# electrosteel2020_10_arrange6_synthboards.net
KiCad netlist of a schematic drawn in EAGLE
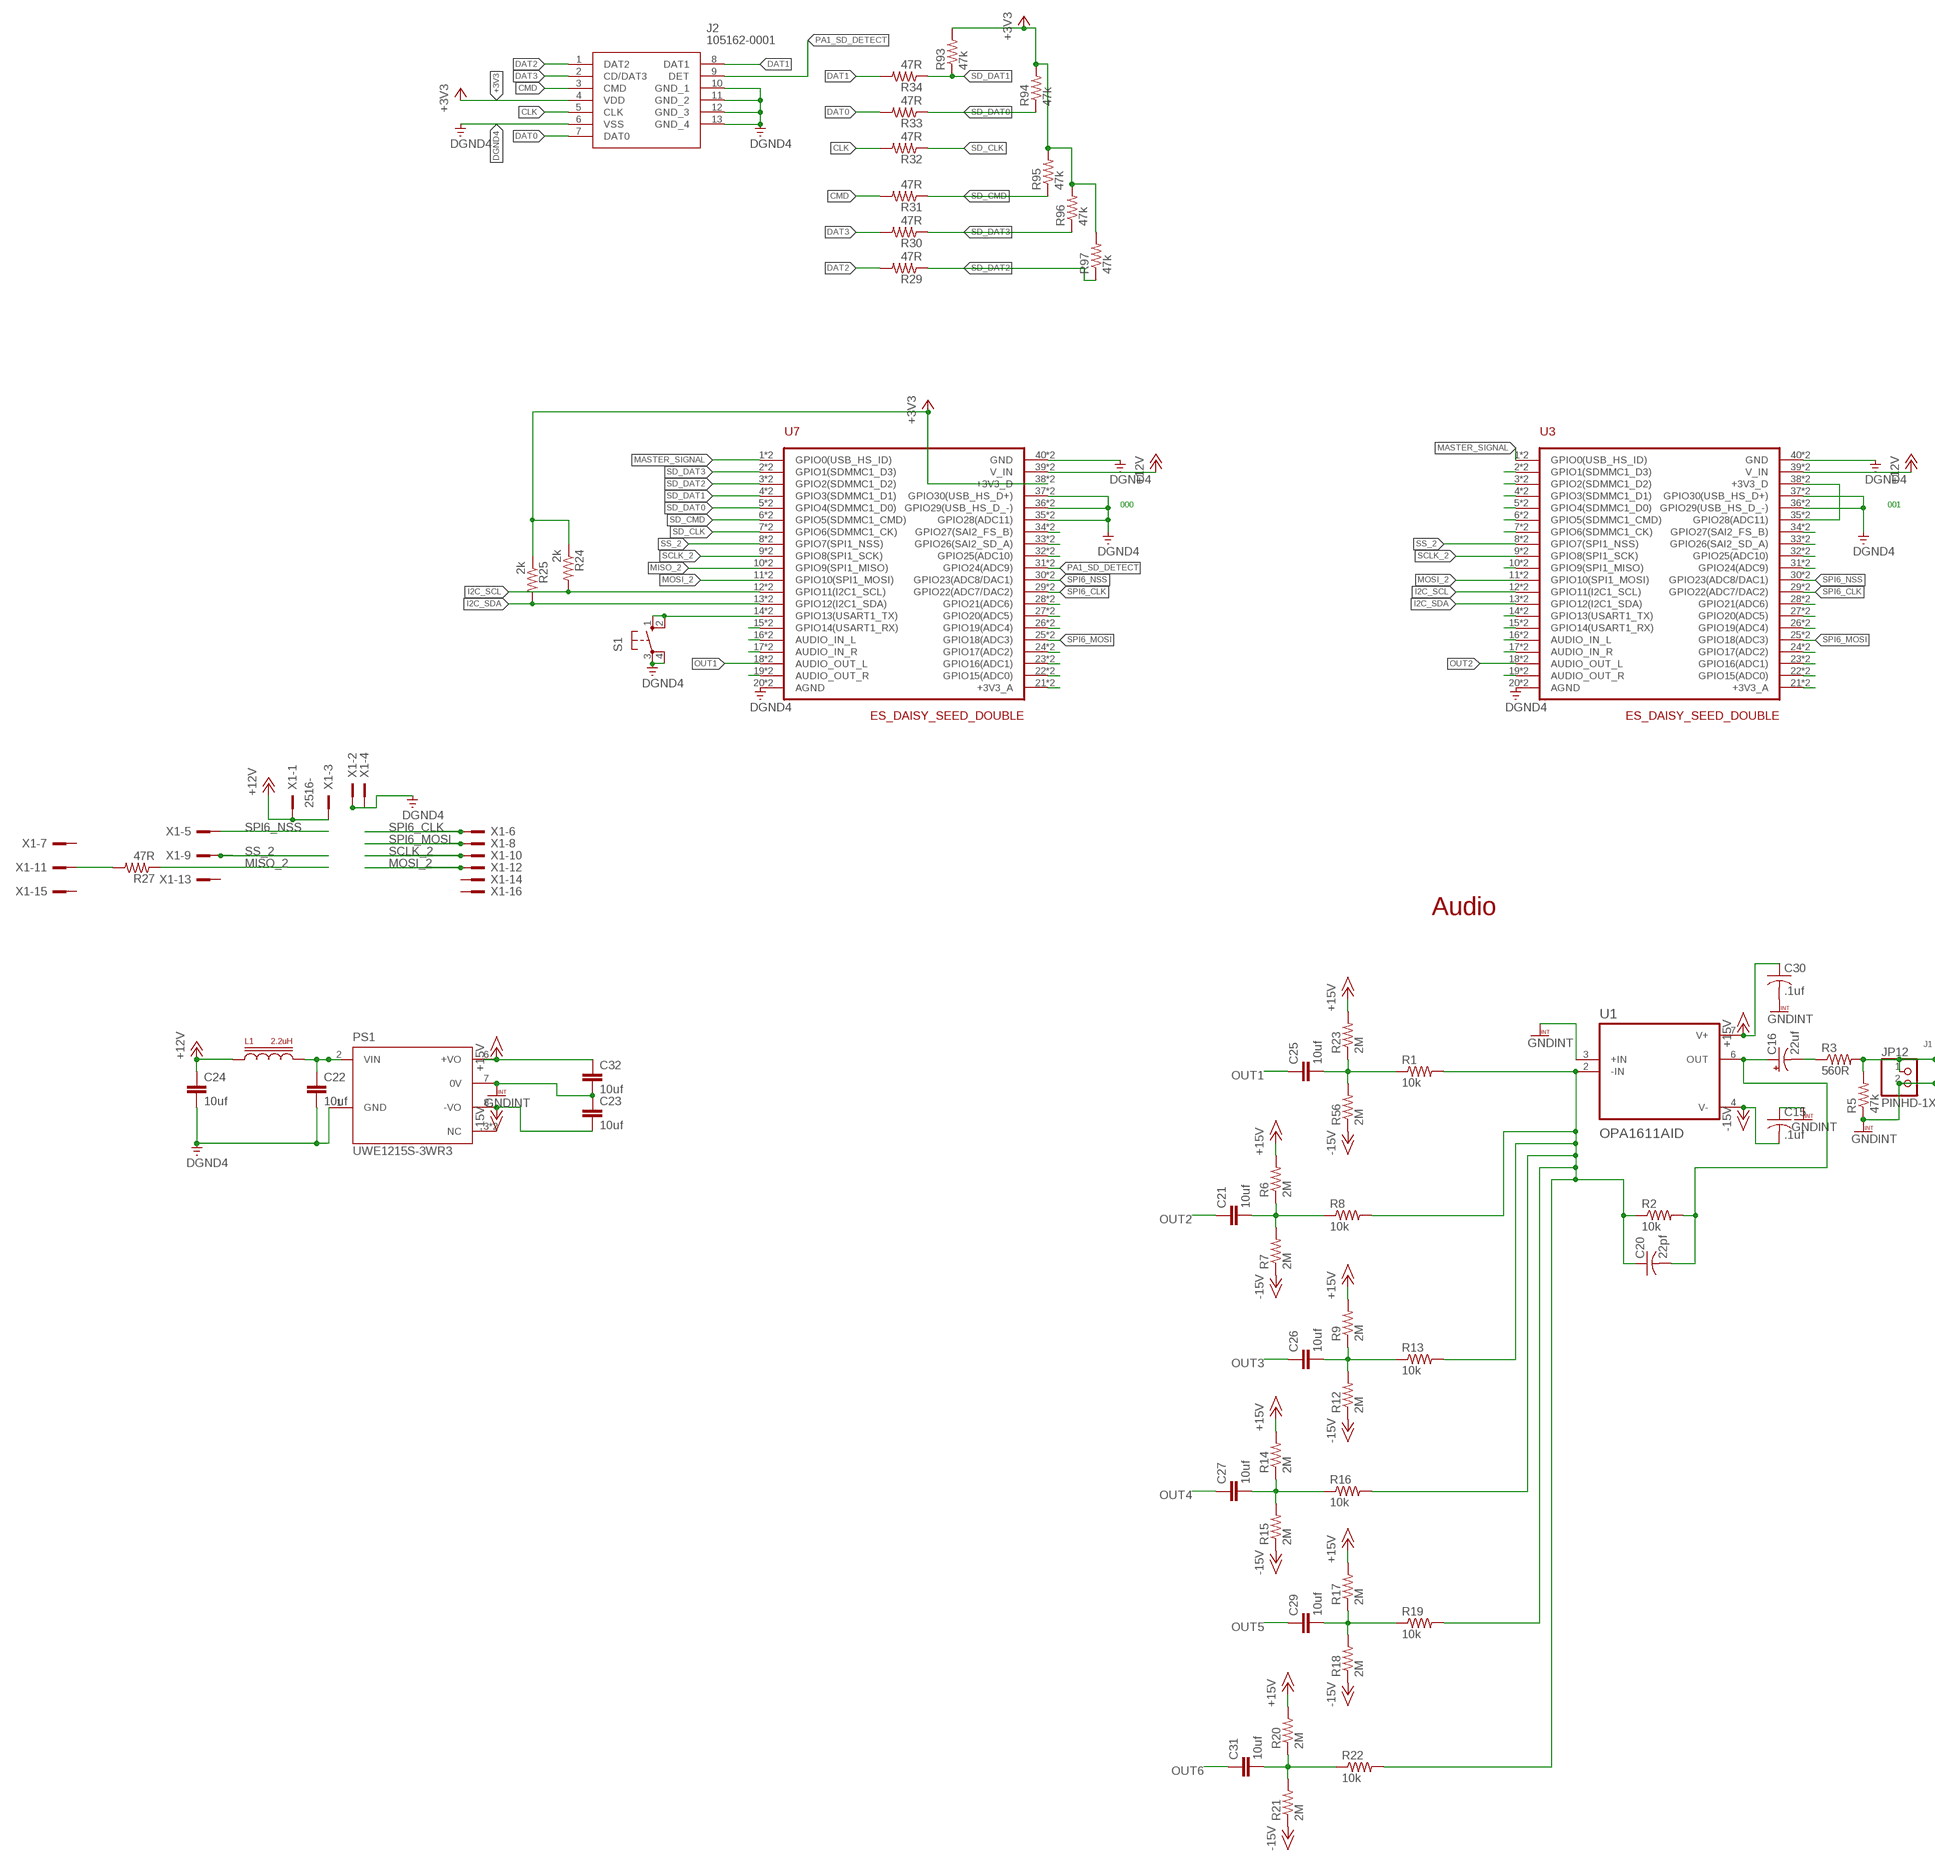
[diagram p0: schematic, sheet 1, part 1 of 2]
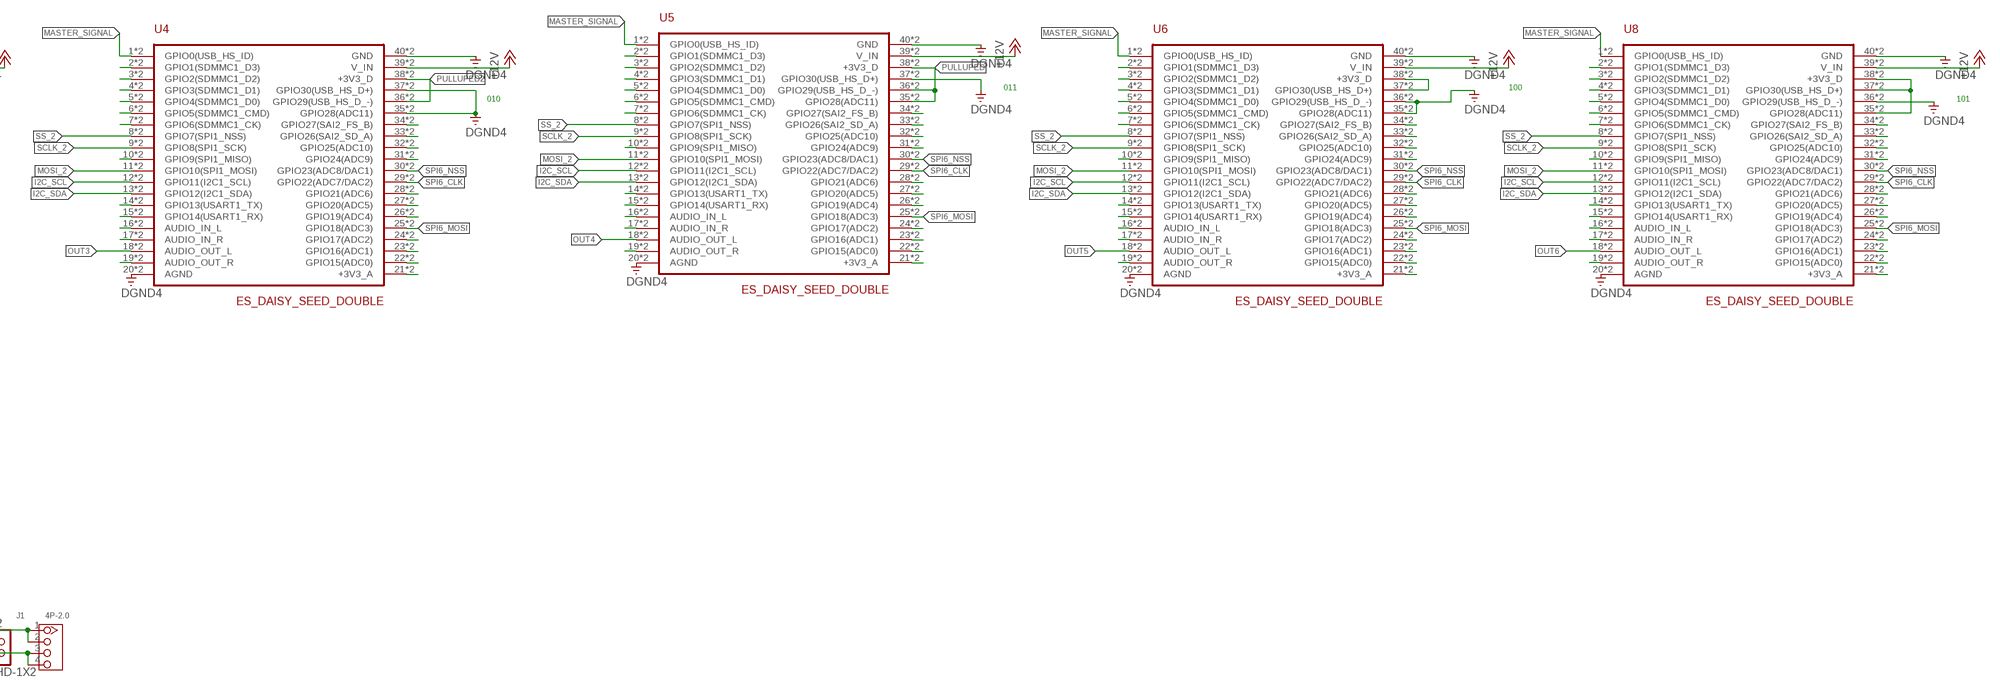
[diagram p1: schematic, sheet 1, part 2 of 2]

(export (version "E")
  (design (tool "Eeschema 10.0.6"))
  (components
    (comp (ref "C15")
      (value ".1uf")
      (footprint "eagle-import:C0603K")
      (fields (field (name "PARTNO") "CC0603KRX7R8BB104"))
      (libsource (lib "eagle-import") (part "C-USC0603K"))
    )
    (comp (ref "C16")
      (value "22uf")
      (footprint "eagle-import:PANASONIC_D")
      (fields (field (name "PARTNO") "EEE-1CA220NP"))
      (libsource (lib "eagle-import") (part "CPOL-USD"))
    )
    (comp (ref "C20")
      (value "22pf")
      (footprint "eagle-import:C0603")
      (fields (field (name "PARTNO") "CC0603JRNPO9BN220"))
      (libsource (lib "eagle-import") (part "rcl_334_C-USC0603"))
    )
    (comp (ref "C21")
      (value "10uf")
      (footprint "eagle-import:C1206K")
      (fields (field (name "PARTNO") "TMK316F106ZL-T"))
      (libsource (lib "eagle-import") (part "C-EUC1206K"))
    )
    (comp (ref "C22")
      (value "10uf")
      (footprint "eagle-import:C1206K")
      (fields (field (name "PARTNO") "TMK316F106ZL-T"))
      (libsource (lib "eagle-import") (part "C-EUC1206K"))
    )
    (comp (ref "C23")
      (value "10uf")
      (footprint "eagle-import:C1206K")
      (fields (field (name "PARTNO") "TMK316F106ZL-T"))
      (libsource (lib "eagle-import") (part "C-EUC1206K"))
    )
    (comp (ref "C24")
      (value "10uf")
      (footprint "eagle-import:C1206K")
      (fields (field (name "PARTNO") "TMK316F106ZL-T"))
      (libsource (lib "eagle-import") (part "C-EUC1206K"))
    )
    (comp (ref "C25")
      (value "10uf")
      (footprint "eagle-import:C1206K")
      (fields (field (name "PARTNO") "TMK316F106ZL-T"))
      (libsource (lib "eagle-import") (part "C-EUC1206K"))
    )
    (comp (ref "C26")
      (value "10uf")
      (footprint "eagle-import:C1206K")
      (fields (field (name "PARTNO") "TMK316F106ZL-T"))
      (libsource (lib "eagle-import") (part "C-EUC1206K"))
    )
    (comp (ref "C27")
      (value "10uf")
      (footprint "eagle-import:C1206K")
      (fields (field (name "PARTNO") "TMK316F106ZL-T"))
      (libsource (lib "eagle-import") (part "C-EUC1206K"))
    )
    (comp (ref "C29")
      (value "10uf")
      (footprint "eagle-import:C1206K")
      (fields (field (name "PARTNO") "TMK316F106ZL-T"))
      (libsource (lib "eagle-import") (part "C-EUC1206K"))
    )
    (comp (ref "C30")
      (value ".1uf")
      (footprint "eagle-import:C0603K")
      (fields (field (name "PARTNO") "CC0603KRX7R8BB104"))
      (libsource (lib "eagle-import") (part "C-USC0603K"))
    )
    (comp (ref "C31")
      (value "10uf")
      (footprint "eagle-import:C1206K")
      (fields (field (name "PARTNO") "TMK316F106ZL-T"))
      (libsource (lib "eagle-import") (part "C-EUC1206K"))
    )
    (comp (ref "C32")
      (value "10uf")
      (footprint "eagle-import:C1206K")
      (fields (field (name "PARTNO") "TMK316F106ZL-T"))
      (libsource (lib "eagle-import") (part "C-EUC1206K"))
    )
    (comp (ref "J1")
      (value "4P-2.0")
      (footprint "eagle-import:HW4-2.0")
      (fields (field (name "PARTNO") "110990030"))
      (libsource (lib "eagle-import") (part "GROVE-CONNECTOR-DIP(4P-2.0)"))
    )
    (comp (ref "J2")
      (value "105162-0001")
      (footprint "eagle-import:105162-0001")
      (fields (field (name "MF") "Molex") (field (name "MP") "1051620001"))
      (libsource (lib "eagle-import") (part "105162-0001"))
    )
    (comp (ref "JP12")
      (value "PINHD-1X2")
      (footprint "eagle-import:1X02")
      (fields (field (name "PARTNO") "*DNP"))
      (libsource (lib "eagle-import") (part "PINHD-1X2"))
    )
    (comp (ref "L1")
      (value "2.2uH")
      (footprint "eagle-import:BOURNS_SRP2010")
      (fields (field (name "PARTNO") "SRP2010-2R2M"))
      (libsource (lib "eagle-import") (part "INDUCTORS"))
    )
    (comp (ref "PS1")
      (value "UWE1215S-3WR3")
      (footprint "eagle-import:CONV_UWE1215S-3WR3")
      (fields
        (field (name "DIGI-KEY_PART_NUMBER") "2725-UWE1215S-3WR3-ND")
        (field (name "MF") "Mornsun America, LLC")
      )
      (libsource (lib "eagle-import") (part "UWE1215S-3WR3"))
    )
    (comp (ref "R1")
      (value "10k")
      (footprint "eagle-import:R0603")
      (fields (field (name "PARTNO") "ESR03EZPF1002"))
      (libsource (lib "eagle-import") (part "Resistor_16378527_R-US_R0603"))
    )
    (comp (ref "R2")
      (value "10k")
      (footprint "eagle-import:R0603")
      (fields (field (name "PARTNO") "ESR03EZPF1002"))
      (libsource (lib "eagle-import") (part "Resistor_16378527_R-US_R0603"))
    )
    (comp (ref "R3")
      (value "560R")
      (footprint "eagle-import:R0603")
      (fields (field (name "PARTNO") "ESR03EZPF5600"))
      (libsource (lib "eagle-import") (part "Resistor_16378527_R-US_R0603"))
    )
    (comp (ref "R5")
      (value "47k")
      (footprint "eagle-import:R0603")
      (fields (field (name "PARTNO") "ESR03EZPJ473"))
      (libsource (lib "eagle-import") (part "Resistor_16378527_R-US_R0603"))
    )
    (comp (ref "R6")
      (value "2M")
      (footprint "eagle-import:R0603")
      (fields (field (name "PARTNO") "RMCF0603FT2M00"))
      (libsource (lib "eagle-import") (part "R-US_R0603"))
    )
    (comp (ref "R7")
      (value "2M")
      (footprint "eagle-import:R0603")
      (fields (field (name "PARTNO") "RMCF0603FT2M00"))
      (libsource (lib "eagle-import") (part "R-US_R0603"))
    )
    (comp (ref "R8")
      (value "10k")
      (footprint "eagle-import:R0603")
      (fields (field (name "PARTNO") "ESR03EZPF1002"))
      (libsource (lib "eagle-import") (part "Resistor_16378527_R-US_R0603"))
    )
    (comp (ref "R9")
      (value "2M")
      (footprint "eagle-import:R0603")
      (fields (field (name "PARTNO") "RMCF0603FT2M00"))
      (libsource (lib "eagle-import") (part "R-US_R0603"))
    )
    (comp (ref "R12")
      (value "2M")
      (footprint "eagle-import:R0603")
      (fields (field (name "PARTNO") "RMCF0603FT2M00"))
      (libsource (lib "eagle-import") (part "R-US_R0603"))
    )
    (comp (ref "R13")
      (value "10k")
      (footprint "eagle-import:R0603")
      (fields (field (name "PARTNO") "ESR03EZPF1002"))
      (libsource (lib "eagle-import") (part "Resistor_16378527_R-US_R0603"))
    )
    (comp (ref "R14")
      (value "2M")
      (footprint "eagle-import:R0603")
      (fields (field (name "PARTNO") "RMCF0603FT2M00"))
      (libsource (lib "eagle-import") (part "R-US_R0603"))
    )
    (comp (ref "R15")
      (value "2M")
      (footprint "eagle-import:R0603")
      (fields (field (name "PARTNO") "RMCF0603FT2M00"))
      (libsource (lib "eagle-import") (part "R-US_R0603"))
    )
    (comp (ref "R16")
      (value "10k")
      (footprint "eagle-import:R0603")
      (fields (field (name "PARTNO") "ESR03EZPF1002"))
      (libsource (lib "eagle-import") (part "Resistor_16378527_R-US_R0603"))
    )
    (comp (ref "R17")
      (value "2M")
      (footprint "eagle-import:R0603")
      (fields (field (name "PARTNO") "RMCF0603FT2M00"))
      (libsource (lib "eagle-import") (part "R-US_R0603"))
    )
    (comp (ref "R18")
      (value "2M")
      (footprint "eagle-import:R0603")
      (fields (field (name "PARTNO") "RMCF0603FT2M00"))
      (libsource (lib "eagle-import") (part "R-US_R0603"))
    )
    (comp (ref "R19")
      (value "10k")
      (footprint "eagle-import:R0603")
      (fields (field (name "PARTNO") "ESR03EZPF1002"))
      (libsource (lib "eagle-import") (part "Resistor_16378527_R-US_R0603"))
    )
    (comp (ref "R20")
      (value "2M")
      (footprint "eagle-import:R0603")
      (fields (field (name "PARTNO") "RMCF0603FT2M00"))
      (libsource (lib "eagle-import") (part "R-US_R0603"))
    )
    (comp (ref "R21")
      (value "2M")
      (footprint "eagle-import:R0603")
      (fields (field (name "PARTNO") "RMCF0603FT2M00"))
      (libsource (lib "eagle-import") (part "R-US_R0603"))
    )
    (comp (ref "R22")
      (value "10k")
      (footprint "eagle-import:R0603")
      (fields (field (name "PARTNO") "ESR03EZPF1002"))
      (libsource (lib "eagle-import") (part "Resistor_16378527_R-US_R0603"))
    )
    (comp (ref "R23")
      (value "2M")
      (footprint "eagle-import:R0603")
      (fields (field (name "PARTNO") "RMCF0603FT2M00"))
      (libsource (lib "eagle-import") (part "R-US_R0603"))
    )
    (comp (ref "R24")
      (value "2k")
      (footprint "eagle-import:R0603")
      (fields (field (name "PARTNO") "ERJ-PA3F2001V"))
      (libsource (lib "eagle-import") (part "rcl_334_R-US_R0603"))
    )
    (comp (ref "R25")
      (value "2k")
      (footprint "eagle-import:R0603")
      (fields (field (name "PARTNO") "ERJ-PA3F2001V"))
      (libsource (lib "eagle-import") (part "rcl_334_R-US_R0603"))
    )
    (comp (ref "R27")
      (value "47R")
      (footprint "eagle-import:R0603")
      (fields (field (name "PARTNO") "RC0603JR-0747RL"))
      (libsource (lib "eagle-import") (part "rcl_334_R-US_R0603"))
    )
    (comp (ref "R29")
      (value "47R")
      (footprint "eagle-import:R0603")
      (fields (field (name "PARTNO") "RC0603JR-0747RL"))
      (libsource (lib "eagle-import") (part "rcl_334_R-US_R0603"))
    )
    (comp (ref "R30")
      (value "47R")
      (footprint "eagle-import:R0603")
      (fields (field (name "PARTNO") "RC0603JR-0747RL"))
      (libsource (lib "eagle-import") (part "rcl_334_R-US_R0603"))
    )
    (comp (ref "R31")
      (value "47R")
      (footprint "eagle-import:R0603")
      (fields (field (name "PARTNO") "RC0603JR-0747RL"))
      (libsource (lib "eagle-import") (part "rcl_334_R-US_R0603"))
    )
    (comp (ref "R32")
      (value "47R")
      (footprint "eagle-import:R0603")
      (fields (field (name "PARTNO") "RC0603JR-0747RL"))
      (libsource (lib "eagle-import") (part "rcl_334_R-US_R0603"))
    )
    (comp (ref "R33")
      (value "47R")
      (footprint "eagle-import:R0603")
      (fields (field (name "PARTNO") "RC0603JR-0747RL"))
      (libsource (lib "eagle-import") (part "rcl_334_R-US_R0603"))
    )
    (comp (ref "R34")
      (value "47R")
      (footprint "eagle-import:R0603")
      (fields (field (name "PARTNO") "RC0603JR-0747RL"))
      (libsource (lib "eagle-import") (part "rcl_334_R-US_R0603"))
    )
    (comp (ref "R56")
      (value "2M")
      (footprint "eagle-import:R0603")
      (fields (field (name "PARTNO") "RMCF0603FT2M00"))
      (libsource (lib "eagle-import") (part "R-US_R0603"))
    )
    (comp (ref "R93")
      (value "47k")
      (footprint "eagle-import:R0603")
      (fields (field (name "PARTNO") "ESR03EZPJ473"))
      (libsource (lib "eagle-import") (part "rcl_R-US_R0603"))
    )
    (comp (ref "R94")
      (value "47k")
      (footprint "eagle-import:R0603")
      (fields (field (name "PARTNO") "ESR03EZPJ473"))
      (libsource (lib "eagle-import") (part "rcl_R-US_R0603"))
    )
    (comp (ref "R95")
      (value "47k")
      (footprint "eagle-import:R0603")
      (fields (field (name "PARTNO") "ESR03EZPJ473"))
      (libsource (lib "eagle-import") (part "rcl_R-US_R0603"))
    )
    (comp (ref "R96")
      (value "47k")
      (footprint "eagle-import:R0603")
      (fields (field (name "PARTNO") "ESR03EZPJ473"))
      (libsource (lib "eagle-import") (part "rcl_R-US_R0603"))
    )
    (comp (ref "R97")
      (value "47k")
      (footprint "eagle-import:R0603")
      (fields (field (name "PARTNO") "ESR03EZPJ473"))
      (libsource (lib "eagle-import") (part "rcl_R-US_R0603"))
    )
    (comp (ref "S1")
      (value "10-XX")
      (footprint "eagle-import:B3F-10XX")
      (fields (field (name "MPN") "B3F-1000"))
      (libsource (lib "eagle-import") (part "10-XX"))
    )
    (comp (ref "U1")
      (value "OPA1611AID")
      (footprint "eagle-import:SOIC127P599X175-8N")
      (fields (field (name "DIGI-KEY_PART_NUMBER") "296-24958-5-ND") (field (name "MF") "Texas Instruments"))
      (libsource (lib "eagle-import") (part "OPA1611AID"))
    )
    (comp (ref "U3")
      (value "ES_DAISY_SEED_DOUBLE")
      (footprint "eagle-import:ES_DAISY_SEED_DOUBLE")
      (fields (field (name "PARTNO") "4840-6004-CP"))
      (libsource (lib "eagle-import") (part "ES_DAISY_SEED_DOUBLE"))
    )
    (comp (ref "U4")
      (value "ES_DAISY_SEED_DOUBLE")
      (footprint "eagle-import:ES_DAISY_SEED_DOUBLE")
      (fields (field (name "PARTNO") "4840-6004-CP"))
      (libsource (lib "eagle-import") (part "ES_DAISY_SEED_DOUBLE"))
    )
    (comp (ref "U5")
      (value "ES_DAISY_SEED_DOUBLE")
      (footprint "eagle-import:ES_DAISY_SEED_DOUBLE")
      (fields (field (name "PARTNO") "4840-6004-CP"))
      (libsource (lib "eagle-import") (part "ES_DAISY_SEED_DOUBLE"))
    )
    (comp (ref "U6")
      (value "ES_DAISY_SEED_DOUBLE")
      (footprint "eagle-import:ES_DAISY_SEED_DOUBLE")
      (fields (field (name "PARTNO") "4840-6004-CP"))
      (libsource (lib "eagle-import") (part "ES_DAISY_SEED_DOUBLE"))
    )
    (comp (ref "U7")
      (value "ES_DAISY_SEED_DOUBLE")
      (footprint "eagle-import:ES_DAISY_SEED_DOUBLE")
      (fields (field (name "PARTNO") "4840-6004-CP"))
      (libsource (lib "eagle-import") (part "ES_DAISY_SEED_DOUBLE"))
    )
    (comp (ref "U8")
      (value "ES_DAISY_SEED_DOUBLE")
      (footprint "eagle-import:ES_DAISY_SEED_DOUBLE")
      (fields (field (name "PARTNO") "4840-6004-CP"))
      (libsource (lib "eagle-import") (part "ES_DAISY_SEED_DOUBLE"))
    )
    (comp (ref "X1")
      (value "2516-")
      (footprint "eagle-import:PAK100_2500-16")
      (fields (field (name "PARTNO") "SBH11-PBPC-D08-ST-BK"))
      (libsource (lib "eagle-import") (part "2516-"))
    )
  )
  (nets
    (net (code "1") (name "+3V3") (class "Default")
      (node (ref "J2") (pin "4") (pinfunction "VDD_4") (pintype "bidirectional"))
      (node (ref "R24") (pin "1") (pinfunction "1_1") (pintype "passive"))
      (node (ref "R25") (pin "1") (pinfunction "1_1") (pintype "passive"))
      (node (ref "R93") (pin "2") (pinfunction "2_2") (pintype "passive"))
      (node (ref "R94") (pin "2") (pinfunction "2_2") (pintype "passive"))
      (node (ref "R95") (pin "2") (pinfunction "2_2") (pintype "passive"))
      (node (ref "R96") (pin "2") (pinfunction "2_2") (pintype "passive"))
      (node (ref "R97") (pin "2") (pinfunction "2_2") (pintype "passive"))
      (node (ref "U7") (pin "38") (pinfunction "+3V3_D_38") (pintype "bidirectional"))
      (node (ref "U7") (pin "B38") (pinfunction "+3V3_D_B38") (pintype "bidirectional"))
    )
    (net (code "2") (name "+12V") (class "Default")
      (node (ref "C24") (pin "1") (pinfunction "1_1") (pintype "passive"))
      (node (ref "L1") (pin "P$1") (pinfunction "P$1_P$1") (pintype "bidirectional"))
      (node (ref "U3") (pin "39") (pinfunction "V_IN_39") (pintype "bidirectional"))
      (node (ref "U3") (pin "B39") (pinfunction "V_IN_B39") (pintype "bidirectional"))
      (node (ref "U4") (pin "39") (pinfunction "V_IN_39") (pintype "bidirectional"))
      (node (ref "U4") (pin "B39") (pinfunction "V_IN_B39") (pintype "bidirectional"))
      (node (ref "U5") (pin "39") (pinfunction "V_IN_39") (pintype "bidirectional"))
      (node (ref "U5") (pin "B39") (pinfunction "V_IN_B39") (pintype "bidirectional"))
      (node (ref "U6") (pin "39") (pinfunction "V_IN_39") (pintype "bidirectional"))
      (node (ref "U6") (pin "B39") (pinfunction "V_IN_B39") (pintype "bidirectional"))
      (node (ref "U7") (pin "39") (pinfunction "V_IN_39") (pintype "bidirectional"))
      (node (ref "U7") (pin "B39") (pinfunction "V_IN_B39") (pintype "bidirectional"))
      (node (ref "U8") (pin "39") (pinfunction "V_IN_39") (pintype "bidirectional"))
      (node (ref "U8") (pin "B39") (pinfunction "V_IN_B39") (pintype "bidirectional"))
      (node (ref "X1") (pin "1") (pinfunction "KL_1") (pintype "passive"))
      (node (ref "X1") (pin "3") (pinfunction "KL_3") (pintype "passive"))
    )
    (net (code "3") (name "+15V") (class "Default")
      (node (ref "C30") (pin "1") (pinfunction "1_1") (pintype "passive"))
      (node (ref "C32") (pin "1") (pinfunction "1_1") (pintype "passive"))
      (node (ref "PS1") (pin "6") (pinfunction "+VO_6") (pintype "output"))
      (node (ref "R14") (pin "2") (pinfunction "2_2") (pintype "passive"))
      (node (ref "R17") (pin "2") (pinfunction "2_2") (pintype "passive"))
      (node (ref "R20") (pin "2") (pinfunction "2_2") (pintype "passive"))
      (node (ref "R23") (pin "2") (pinfunction "2_2") (pintype "passive"))
      (node (ref "R6") (pin "2") (pinfunction "2_2") (pintype "passive"))
      (node (ref "R9") (pin "2") (pinfunction "2_2") (pintype "passive"))
      (node (ref "U1") (pin "7") (pinfunction "V+_7") (pintype "power_in"))
    )
    (net (code "4") (name "-15V") (class "Default")
      (node (ref "C15") (pin "2") (pinfunction "2_2") (pintype "passive"))
      (node (ref "C23") (pin "2") (pinfunction "2_2") (pintype "passive"))
      (node (ref "PS1") (pin "8") (pinfunction "-VO_8") (pintype "output"))
      (node (ref "R12") (pin "1") (pinfunction "1_1") (pintype "passive"))
      (node (ref "R15") (pin "1") (pinfunction "1_1") (pintype "passive"))
      (node (ref "R18") (pin "1") (pinfunction "1_1") (pintype "passive"))
      (node (ref "R21") (pin "1") (pinfunction "1_1") (pintype "passive"))
      (node (ref "R56") (pin "1") (pinfunction "1_1") (pintype "passive"))
      (node (ref "R7") (pin "1") (pinfunction "1_1") (pintype "passive"))
      (node (ref "U1") (pin "4") (pinfunction "V-_4") (pintype "power_in"))
    )
    (net (code "5") (name "CLK") (class "Default")
      (node (ref "J2") (pin "5") (pinfunction "CLK_5") (pintype "bidirectional"))
      (node (ref "R32") (pin "2") (pinfunction "2_2") (pintype "passive"))
    )
    (net (code "6") (name "CMD") (class "Default")
      (node (ref "J2") (pin "3") (pinfunction "CMD_3") (pintype "bidirectional"))
      (node (ref "R31") (pin "2") (pinfunction "2_2") (pintype "passive"))
    )
    (net (code "7") (name "DAT0") (class "Default")
      (node (ref "J2") (pin "7") (pinfunction "DAT0_7") (pintype "bidirectional"))
      (node (ref "R33") (pin "2") (pinfunction "2_2") (pintype "passive"))
    )
    (net (code "8") (name "DAT1") (class "Default")
      (node (ref "J2") (pin "8") (pinfunction "DAT1_8") (pintype "bidirectional"))
      (node (ref "R34") (pin "2") (pinfunction "2_2") (pintype "passive"))
    )
    (net (code "9") (name "DAT2") (class "Default")
      (node (ref "J2") (pin "1") (pinfunction "DAT2_1") (pintype "bidirectional"))
      (node (ref "R29") (pin "2") (pinfunction "2_2") (pintype "passive"))
    )
    (net (code "10") (name "DAT3") (class "Default")
      (node (ref "J2") (pin "2") (pinfunction "CD/DAT3_2") (pintype "bidirectional"))
      (node (ref "R30") (pin "2") (pinfunction "2_2") (pintype "passive"))
    )
    (net (code "11") (name "DGND4") (class "Default")
      (node (ref "C22") (pin "2") (pinfunction "2_2") (pintype "passive"))
      (node (ref "C24") (pin "2") (pinfunction "2_2") (pintype "passive"))
      (node (ref "J2") (pin "10") (pinfunction "GND_1_10") (pintype "bidirectional"))
      (node (ref "J2") (pin "11") (pinfunction "GND_2_11") (pintype "bidirectional"))
      (node (ref "J2") (pin "12") (pinfunction "GND_3_12") (pintype "bidirectional"))
      (node (ref "J2") (pin "13") (pinfunction "GND_4_13") (pintype "bidirectional"))
      (node (ref "J2") (pin "6") (pinfunction "VSS_6") (pintype "bidirectional"))
      (node (ref "PS1") (pin "1") (pinfunction "GND_1") (pintype "power_in"))
      (node (ref "S1") (pin "3") (pinfunction "P_3") (pintype "passive"))
      (node (ref "S1") (pin "4") (pinfunction "P1_4") (pintype "passive"))
      (node (ref "U3") (pin "20") (pinfunction "AGND_20") (pintype "bidirectional"))
      (node (ref "U3") (pin "36") (pinfunction "GPIO29(USB_HS_D_-)_36") (pintype "bidirectional"))
      (node (ref "U3") (pin "37") (pinfunction "GPIO30(USB_HS_D+)_37") (pintype "bidirectional"))
      (node (ref "U3") (pin "40") (pinfunction "GND_40") (pintype "bidirectional"))
      (node (ref "U3") (pin "B20") (pinfunction "AGND_B20") (pintype "bidirectional"))
      (node (ref "U3") (pin "B36") (pinfunction "GPIO29(USB_HS_D_-)_B36") (pintype "bidirectional"))
      (node (ref "U3") (pin "B37") (pinfunction "GPIO30(USB_HS_D+)_B37") (pintype "bidirectional"))
      (node (ref "U3") (pin "B40") (pinfunction "GND_B40") (pintype "bidirectional"))
      (node (ref "U4") (pin "20") (pinfunction "AGND_20") (pintype "bidirectional"))
      (node (ref "U4") (pin "35") (pinfunction "GPIO28(ADC11)_35") (pintype "bidirectional"))
      (node (ref "U4") (pin "37") (pinfunction "GPIO30(USB_HS_D+)_37") (pintype "bidirectional"))
      (node (ref "U4") (pin "40") (pinfunction "GND_40") (pintype "bidirectional"))
      (node (ref "U4") (pin "B20") (pinfunction "AGND_B20") (pintype "bidirectional"))
      (node (ref "U4") (pin "B35") (pinfunction "GPIO28(ADC11)_B35") (pintype "bidirectional"))
      (node (ref "U4") (pin "B37") (pinfunction "GPIO30(USB_HS_D+)_B37") (pintype "bidirectional"))
      (node (ref "U4") (pin "B40") (pinfunction "GND_B40") (pintype "bidirectional"))
      (node (ref "U5") (pin "20") (pinfunction "AGND_20") (pintype "bidirectional"))
      (node (ref "U5") (pin "37") (pinfunction "GPIO30(USB_HS_D+)_37") (pintype "bidirectional"))
      (node (ref "U5") (pin "40") (pinfunction "GND_40") (pintype "bidirectional"))
      (node (ref "U5") (pin "B20") (pinfunction "AGND_B20") (pintype "bidirectional"))
      (node (ref "U5") (pin "B37") (pinfunction "GPIO30(USB_HS_D+)_B37") (pintype "bidirectional"))
      (node (ref "U5") (pin "B40") (pinfunction "GND_B40") (pintype "bidirectional"))
      (node (ref "U6") (pin "20") (pinfunction "AGND_20") (pintype "bidirectional"))
      (node (ref "U6") (pin "35") (pinfunction "GPIO28(ADC11)_35") (pintype "bidirectional"))
      (node (ref "U6") (pin "36") (pinfunction "GPIO29(USB_HS_D_-)_36") (pintype "bidirectional"))
      (node (ref "U6") (pin "40") (pinfunction "GND_40") (pintype "bidirectional"))
      (node (ref "U6") (pin "B20") (pinfunction "AGND_B20") (pintype "bidirectional"))
      (node (ref "U6") (pin "B35") (pinfunction "GPIO28(ADC11)_B35") (pintype "bidirectional"))
      (node (ref "U6") (pin "B36") (pinfunction "GPIO29(USB_HS_D_-)_B36") (pintype "bidirectional"))
      (node (ref "U6") (pin "B40") (pinfunction "GND_B40") (pintype "bidirectional"))
      (node (ref "U7") (pin "20") (pinfunction "AGND_20") (pintype "bidirectional"))
      (node (ref "U7") (pin "35") (pinfunction "GPIO28(ADC11)_35") (pintype "bidirectional"))
      (node (ref "U7") (pin "36") (pinfunction "GPIO29(USB_HS_D_-)_36") (pintype "bidirectional"))
      (node (ref "U7") (pin "37") (pinfunction "GPIO30(USB_HS_D+)_37") (pintype "bidirectional"))
      (node (ref "U7") (pin "40") (pinfunction "GND_40") (pintype "bidirectional"))
      (node (ref "U7") (pin "B20") (pinfunction "AGND_B20") (pintype "bidirectional"))
      (node (ref "U7") (pin "B35") (pinfunction "GPIO28(ADC11)_B35") (pintype "bidirectional"))
      (node (ref "U7") (pin "B36") (pinfunction "GPIO29(USB_HS_D_-)_B36") (pintype "bidirectional"))
      (node (ref "U7") (pin "B37") (pinfunction "GPIO30(USB_HS_D+)_B37") (pintype "bidirectional"))
      (node (ref "U7") (pin "B40") (pinfunction "GND_B40") (pintype "bidirectional"))
      (node (ref "U8") (pin "20") (pinfunction "AGND_20") (pintype "bidirectional"))
      (node (ref "U8") (pin "36") (pinfunction "GPIO29(USB_HS_D_-)_36") (pintype "bidirectional"))
      (node (ref "U8") (pin "40") (pinfunction "GND_40") (pintype "bidirectional"))
      (node (ref "U8") (pin "B20") (pinfunction "AGND_B20") (pintype "bidirectional"))
      (node (ref "U8") (pin "B36") (pinfunction "GPIO29(USB_HS_D_-)_B36") (pintype "bidirectional"))
      (node (ref "U8") (pin "B40") (pinfunction "GND_B40") (pintype "bidirectional"))
      (node (ref "X1") (pin "2") (pinfunction "KL_2") (pintype "passive"))
      (node (ref "X1") (pin "4") (pinfunction "KL_4") (pintype "passive"))
    )
    (net (code "12") (name "GNDINT") (class "Default")
      (node (ref "C15") (pin "1") (pinfunction "1_1") (pintype "passive"))
      (node (ref "C23") (pin "1") (pinfunction "1_1") (pintype "passive"))
      (node (ref "C30") (pin "2") (pinfunction "2_2") (pintype "passive"))
      (node (ref "C32") (pin "2") (pinfunction "2_2") (pintype "passive"))
      (node (ref "J1") (pin "3") (pinfunction "3_3") (pintype "bidirectional"))
      (node (ref "J1") (pin "4") (pinfunction "4_4") (pintype "bidirectional"))
      (node (ref "JP12") (pin "2") (pinfunction "2_2") (pintype "passive"))
      (node (ref "PS1") (pin "7") (pinfunction "0V_7") (pintype "passive"))
      (node (ref "R5") (pin "1") (pinfunction "1_1") (pintype "passive"))
      (node (ref "U1") (pin "3") (pinfunction "+IN_3") (pintype "input"))
    )
    (net (code "13") (name "I2C_SCL") (class "Default")
      (node (ref "R24") (pin "2") (pinfunction "2_2") (pintype "passive"))
      (node (ref "U3") (pin "12") (pinfunction "GPIO11(I2C1_SCL)_12") (pintype "bidirectional"))
      (node (ref "U3") (pin "B12") (pinfunction "GPIO11(I2C1_SCL)_B12") (pintype "bidirectional"))
      (node (ref "U4") (pin "12") (pinfunction "GPIO11(I2C1_SCL)_12") (pintype "bidirectional"))
      (node (ref "U4") (pin "B12") (pinfunction "GPIO11(I2C1_SCL)_B12") (pintype "bidirectional"))
      (node (ref "U5") (pin "12") (pinfunction "GPIO11(I2C1_SCL)_12") (pintype "bidirectional"))
      (node (ref "U5") (pin "B12") (pinfunction "GPIO11(I2C1_SCL)_B12") (pintype "bidirectional"))
      (node (ref "U6") (pin "12") (pinfunction "GPIO11(I2C1_SCL)_12") (pintype "bidirectional"))
      (node (ref "U6") (pin "B12") (pinfunction "GPIO11(I2C1_SCL)_B12") (pintype "bidirectional"))
      (node (ref "U7") (pin "12") (pinfunction "GPIO11(I2C1_SCL)_12") (pintype "bidirectional"))
      (node (ref "U7") (pin "B12") (pinfunction "GPIO11(I2C1_SCL)_B12") (pintype "bidirectional"))
      (node (ref "U8") (pin "12") (pinfunction "GPIO11(I2C1_SCL)_12") (pintype "bidirectional"))
      (node (ref "U8") (pin "B12") (pinfunction "GPIO11(I2C1_SCL)_B12") (pintype "bidirectional"))
    )
    (net (code "14") (name "I2C_SDA") (class "Default")
      (node (ref "R25") (pin "2") (pinfunction "2_2") (pintype "passive"))
      (node (ref "U3") (pin "13") (pinfunction "GPIO12(I2C1_SDA)_13") (pintype "bidirectional"))
      (node (ref "U3") (pin "B13") (pinfunction "GPIO12(I2C1_SDA)_B13") (pintype "bidirectional"))
      (node (ref "U4") (pin "13") (pinfunction "GPIO12(I2C1_SDA)_13") (pintype "bidirectional"))
      (node (ref "U4") (pin "B13") (pinfunction "GPIO12(I2C1_SDA)_B13") (pintype "bidirectional"))
      (node (ref "U5") (pin "13") (pinfunction "GPIO12(I2C1_SDA)_13") (pintype "bidirectional"))
      (node (ref "U5") (pin "B13") (pinfunction "GPIO12(I2C1_SDA)_B13") (pintype "bidirectional"))
      (node (ref "U6") (pin "13") (pinfunction "GPIO12(I2C1_SDA)_13") (pintype "bidirectional"))
      (node (ref "U6") (pin "B13") (pinfunction "GPIO12(I2C1_SDA)_B13") (pintype "bidirectional"))
      (node (ref "U7") (pin "13") (pinfunction "GPIO12(I2C1_SDA)_13") (pintype "bidirectional"))
      (node (ref "U7") (pin "B13") (pinfunction "GPIO12(I2C1_SDA)_B13") (pintype "bidirectional"))
      (node (ref "U8") (pin "13") (pinfunction "GPIO12(I2C1_SDA)_13") (pintype "bidirectional"))
      (node (ref "U8") (pin "B13") (pinfunction "GPIO12(I2C1_SDA)_B13") (pintype "bidirectional"))
    )
    (net (code "15") (name "MASTER_SIGNAL") (class "Default")
      (node (ref "U3") (pin "1") (pinfunction "GPIO0(USB_HS_ID)_1") (pintype "bidirectional"))
      (node (ref "U3") (pin "B1") (pinfunction "GPIO0(USB_HS_ID)_B1") (pintype "bidirectional"))
      (node (ref "U4") (pin "1") (pinfunction "GPIO0(USB_HS_ID)_1") (pintype "bidirectional"))
      (node (ref "U4") (pin "B1") (pinfunction "GPIO0(USB_HS_ID)_B1") (pintype "bidirectional"))
      (node (ref "U5") (pin "1") (pinfunction "GPIO0(USB_HS_ID)_1") (pintype "bidirectional"))
      (node (ref "U5") (pin "B1") (pinfunction "GPIO0(USB_HS_ID)_B1") (pintype "bidirectional"))
      (node (ref "U6") (pin "1") (pinfunction "GPIO0(USB_HS_ID)_1") (pintype "bidirectional"))
      (node (ref "U6") (pin "B1") (pinfunction "GPIO0(USB_HS_ID)_B1") (pintype "bidirectional"))
      (node (ref "U7") (pin "1") (pinfunction "GPIO0(USB_HS_ID)_1") (pintype "bidirectional"))
      (node (ref "U7") (pin "B1") (pinfunction "GPIO0(USB_HS_ID)_B1") (pintype "bidirectional"))
      (node (ref "U8") (pin "1") (pinfunction "GPIO0(USB_HS_ID)_1") (pintype "bidirectional"))
      (node (ref "U8") (pin "B1") (pinfunction "GPIO0(USB_HS_ID)_B1") (pintype "bidirectional"))
    )
    (net (code "16") (name "MISO_2") (class "Default")
      (node (ref "R27") (pin "1") (pinfunction "1_1") (pintype "passive"))
      (node (ref "U7") (pin "10") (pinfunction "GPIO9(SPI1_MISO)_10") (pintype "bidirectional"))
      (node (ref "U7") (pin "B10") (pinfunction "GPIO9(SPI1_MISO)_B10") (pintype "bidirectional"))
    )
    (net (code "17") (name "MOSI_2") (class "Default")
      (node (ref "U3") (pin "11") (pinfunction "GPIO10(SPI1_MOSI)_11") (pintype "bidirectional"))
      (node (ref "U3") (pin "B11") (pinfunction "GPIO10(SPI1_MOSI)_B11") (pintype "bidirectional"))
      (node (ref "U4") (pin "11") (pinfunction "GPIO10(SPI1_MOSI)_11") (pintype "bidirectional"))
      (node (ref "U4") (pin "B11") (pinfunction "GPIO10(SPI1_MOSI)_B11") (pintype "bidirectional"))
      (node (ref "U5") (pin "11") (pinfunction "GPIO10(SPI1_MOSI)_11") (pintype "bidirectional"))
      (node (ref "U5") (pin "B11") (pinfunction "GPIO10(SPI1_MOSI)_B11") (pintype "bidirectional"))
      (node (ref "U6") (pin "11") (pinfunction "GPIO10(SPI1_MOSI)_11") (pintype "bidirectional"))
      (node (ref "U6") (pin "B11") (pinfunction "GPIO10(SPI1_MOSI)_B11") (pintype "bidirectional"))
      (node (ref "U7") (pin "11") (pinfunction "GPIO10(SPI1_MOSI)_11") (pintype "bidirectional"))
      (node (ref "U7") (pin "B11") (pinfunction "GPIO10(SPI1_MOSI)_B11") (pintype "bidirectional"))
      (node (ref "U8") (pin "11") (pinfunction "GPIO10(SPI1_MOSI)_11") (pintype "bidirectional"))
      (node (ref "U8") (pin "B11") (pinfunction "GPIO10(SPI1_MOSI)_B11") (pintype "bidirectional"))
      (node (ref "X1") (pin "12") (pinfunction "KL_12") (pintype "passive"))
    )
    (net (code "18") (name "Net-(C16-Pad-)") (class "Default")
      (node (ref "C16") (pin "-") (pinfunction "-_-") (pintype "passive"))
      (node (ref "R3") (pin "1") (pinfunction "1_1") (pintype "passive"))
    )
    (net (code "19") (name "Net-(C21-Pad2)") (class "Default")
      (node (ref "C21") (pin "2") (pinfunction "2_2") (pintype "passive"))
      (node (ref "R6") (pin "1") (pinfunction "1_1") (pintype "passive"))
      (node (ref "R7") (pin "2") (pinfunction "2_2") (pintype "passive"))
      (node (ref "R8") (pin "1") (pinfunction "1_1") (pintype "passive"))
    )
    (net (code "20") (name "Net-(C25-Pad2)") (class "Default")
      (node (ref "C25") (pin "2") (pinfunction "2_2") (pintype "passive"))
      (node (ref "R1") (pin "1") (pinfunction "1_1") (pintype "passive"))
      (node (ref "R23") (pin "1") (pinfunction "1_1") (pintype "passive"))
      (node (ref "R56") (pin "2") (pinfunction "2_2") (pintype "passive"))
    )
    (net (code "21") (name "Net-(C26-Pad2)") (class "Default")
      (node (ref "C26") (pin "2") (pinfunction "2_2") (pintype "passive"))
      (node (ref "R12") (pin "2") (pinfunction "2_2") (pintype "passive"))
      (node (ref "R13") (pin "1") (pinfunction "1_1") (pintype "passive"))
      (node (ref "R9") (pin "1") (pinfunction "1_1") (pintype "passive"))
    )
    (net (code "22") (name "Net-(C27-Pad2)") (class "Default")
      (node (ref "C27") (pin "2") (pinfunction "2_2") (pintype "passive"))
      (node (ref "R14") (pin "1") (pinfunction "1_1") (pintype "passive"))
      (node (ref "R15") (pin "2") (pinfunction "2_2") (pintype "passive"))
      (node (ref "R16") (pin "1") (pinfunction "1_1") (pintype "passive"))
    )
    (net (code "23") (name "Net-(C29-Pad2)") (class "Default")
      (node (ref "C29") (pin "2") (pinfunction "2_2") (pintype "passive"))
      (node (ref "R17") (pin "1") (pinfunction "1_1") (pintype "passive"))
      (node (ref "R18") (pin "2") (pinfunction "2_2") (pintype "passive"))
      (node (ref "R19") (pin "1") (pinfunction "1_1") (pintype "passive"))
    )
    (net (code "24") (name "Net-(C31-Pad2)") (class "Default")
      (node (ref "C31") (pin "2") (pinfunction "2_2") (pintype "passive"))
      (node (ref "R20") (pin "1") (pinfunction "1_1") (pintype "passive"))
      (node (ref "R21") (pin "2") (pinfunction "2_2") (pintype "passive"))
      (node (ref "R22") (pin "1") (pinfunction "1_1") (pintype "passive"))
    )
    (net (code "25") (name "Net-(J1-Pad1)") (class "Default")
      (node (ref "J1") (pin "1") (pinfunction "1_1") (pintype "bidirectional"))
      (node (ref "J1") (pin "2") (pinfunction "2_2") (pintype "bidirectional"))
      (node (ref "JP12") (pin "1") (pinfunction "1_1") (pintype "passive"))
      (node (ref "R3") (pin "2") (pinfunction "2_2") (pintype "passive"))
      (node (ref "R5") (pin "2") (pinfunction "2_2") (pintype "passive"))
    )
    (net (code "26") (name "Net-(PS1-VIN)") (class "Default")
      (node (ref "C22") (pin "1") (pinfunction "1_1") (pintype "passive"))
      (node (ref "L1") (pin "P$2") (pinfunction "P$2_P$2") (pintype "bidirectional"))
      (node (ref "PS1") (pin "2") (pinfunction "VIN_2") (pintype "input"))
    )
    (net (code "27") (name "Net-(S1-S)") (class "Default")
      (node (ref "S1") (pin "1") (pinfunction "S_1") (pintype "passive"))
      (node (ref "S1") (pin "2") (pinfunction "S1_2") (pintype "passive"))
      (node (ref "U7") (pin "14") (pinfunction "GPIO13(USART1_TX)_14") (pintype "bidirectional"))
      (node (ref "U7") (pin "B14") (pinfunction "GPIO13(USART1_TX)_B14") (pintype "bidirectional"))
    )
    (net (code "28") (name "Net-(U1--IN)") (class "Default")
      (node (ref "C20") (pin "1") (pinfunction "1_1") (pintype "passive"))
      (node (ref "R1") (pin "2") (pinfunction "2_2") (pintype "passive"))
      (node (ref "R13") (pin "2") (pinfunction "2_2") (pintype "passive"))
      (node (ref "R16") (pin "2") (pinfunction "2_2") (pintype "passive"))
      (node (ref "R19") (pin "2") (pinfunction "2_2") (pintype "passive"))
      (node (ref "R2") (pin "1") (pinfunction "1_1") (pintype "passive"))
      (node (ref "R22") (pin "2") (pinfunction "2_2") (pintype "passive"))
      (node (ref "R8") (pin "2") (pinfunction "2_2") (pintype "passive"))
      (node (ref "U1") (pin "2") (pinfunction "-IN_2") (pintype "input"))
    )
    (net (code "29") (name "Net-(U1-OUT)") (class "Default")
      (node (ref "C16") (pin "+") (pinfunction "+_+") (pintype "passive"))
      (node (ref "C20") (pin "2") (pinfunction "2_2") (pintype "passive"))
      (node (ref "R2") (pin "2") (pinfunction "2_2") (pintype "passive"))
      (node (ref "U1") (pin "6") (pinfunction "OUT_6") (pintype "output"))
    )
    (net (code "30") (name "Net-(U3-+3V3_A-Pad21)") (class "Default")
      (node (ref "U3") (pin "21") (pinfunction "+3V3_A_21") (pintype "bidirectional"))
      (node (ref "U3") (pin "B21") (pinfunction "+3V3_A_B21") (pintype "bidirectional"))
    )
    (net (code "31") (name "Net-(U3-+3V3_D-Pad38)") (class "Default")
      (node (ref "U3") (pin "35") (pinfunction "GPIO28(ADC11)_35") (pintype "bidirectional"))
      (node (ref "U3") (pin "38") (pinfunction "+3V3_D_38") (pintype "bidirectional"))
      (node (ref "U3") (pin "B35") (pinfunction "GPIO28(ADC11)_B35") (pintype "bidirectional"))
      (node (ref "U3") (pin "B38") (pinfunction "+3V3_D_B38") (pintype "bidirectional"))
    )
    (net (code "32") (name "Net-(U3-AUDIO_IN_L-Pad16)") (class "Default")
      (node (ref "U3") (pin "16") (pinfunction "AUDIO_IN_L_16") (pintype "bidirectional"))
      (node (ref "U3") (pin "B16") (pinfunction "AUDIO_IN_L_B16") (pintype "bidirectional"))
    )
    (net (code "33") (name "Net-(U3-AUDIO_IN_R-Pad17)") (class "Default")
      (node (ref "U3") (pin "17") (pinfunction "AUDIO_IN_R_17") (pintype "bidirectional"))
      (node (ref "U3") (pin "B17") (pinfunction "AUDIO_IN_R_B17") (pintype "bidirectional"))
    )
    (net (code "34") (name "Net-(U3-AUDIO_OUT_R-Pad19)") (class "Default")
      (node (ref "U3") (pin "19") (pinfunction "AUDIO_OUT_R_19") (pintype "bidirectional"))
      (node (ref "U3") (pin "B19") (pinfunction "AUDIO_OUT_R_B19") (pintype "bidirectional"))
    )
    (net (code "35") (name "Net-(U3-GPIO1(SDMMC1_D3)-Pad2)") (class "Default")
      (node (ref "U3") (pin "2") (pinfunction "GPIO1(SDMMC1_D3)_2") (pintype "bidirectional"))
      (node (ref "U3") (pin "B2") (pinfunction "GPIO1(SDMMC1_D3)_B2") (pintype "bidirectional"))
    )
    (net (code "36") (name "Net-(U3-GPIO2(SDMMC1_D2)-Pad3)") (class "Default")
      (node (ref "U3") (pin "3") (pinfunction "GPIO2(SDMMC1_D2)_3") (pintype "bidirectional"))
      (node (ref "U3") (pin "B3") (pinfunction "GPIO2(SDMMC1_D2)_B3") (pintype "bidirectional"))
    )
    (net (code "37") (name "Net-(U3-GPIO3(SDMMC1_D1)-Pad4)") (class "Default")
      (node (ref "U3") (pin "4") (pinfunction "GPIO3(SDMMC1_D1)_4") (pintype "bidirectional"))
      (node (ref "U3") (pin "B4") (pinfunction "GPIO3(SDMMC1_D1)_B4") (pintype "bidirectional"))
    )
    (net (code "38") (name "Net-(U3-GPIO4(SDMMC1_D0)-Pad5)") (class "Default")
      (node (ref "U3") (pin "5") (pinfunction "GPIO4(SDMMC1_D0)_5") (pintype "bidirectional"))
      (node (ref "U3") (pin "B5") (pinfunction "GPIO4(SDMMC1_D0)_B5") (pintype "bidirectional"))
    )
    (net (code "39") (name "Net-(U3-GPIO5(SDMMC1_CMD)-Pad6)") (class "Default")
      (node (ref "U3") (pin "6") (pinfunction "GPIO5(SDMMC1_CMD)_6") (pintype "bidirectional"))
      (node (ref "U3") (pin "B6") (pinfunction "GPIO5(SDMMC1_CMD)_B6") (pintype "bidirectional"))
    )
    (net (code "40") (name "Net-(U3-GPIO6(SDMMC1_CK)-Pad7)") (class "Default")
      (node (ref "U3") (pin "7") (pinfunction "GPIO6(SDMMC1_CK)_7") (pintype "bidirectional"))
      (node (ref "U3") (pin "B7") (pinfunction "GPIO6(SDMMC1_CK)_B7") (pintype "bidirectional"))
    )
    (net (code "41") (name "Net-(U3-GPIO9(SPI1_MISO)-Pad10)") (class "Default")
      (node (ref "U3") (pin "10") (pinfunction "GPIO9(SPI1_MISO)_10") (pintype "bidirectional"))
      (node (ref "U3") (pin "B10") (pinfunction "GPIO9(SPI1_MISO)_B10") (pintype "bidirectional"))
    )
    (net (code "42") (name "Net-(U3-GPIO13(USART1_TX)-Pad14)") (class "Default")
      (node (ref "U3") (pin "14") (pinfunction "GPIO13(USART1_TX)_14") (pintype "bidirectional"))
      (node (ref "U3") (pin "B14") (pinfunction "GPIO13(USART1_TX)_B14") (pintype "bidirectional"))
    )
    (net (code "43") (name "Net-(U3-GPIO14(USART1_RX)-Pad15)") (class "Default")
      (node (ref "U3") (pin "15") (pinfunction "GPIO14(USART1_RX)_15") (pintype "bidirectional"))
      (node (ref "U3") (pin "B15") (pinfunction "GPIO14(USART1_RX)_B15") (pintype "bidirectional"))
    )
    (net (code "44") (name "Net-(U3-GPIO15(ADC0)-Pad22)") (class "Default")
      (node (ref "U3") (pin "22") (pinfunction "GPIO15(ADC0)_22") (pintype "bidirectional"))
      (node (ref "U3") (pin "B22") (pinfunction "GPIO15(ADC0)_B22") (pintype "bidirectional"))
    )
    (net (code "45") (name "Net-(U3-GPIO16(ADC1)-Pad23)") (class "Default")
      (node (ref "U3") (pin "23") (pinfunction "GPIO16(ADC1)_23") (pintype "bidirectional"))
      (node (ref "U3") (pin "B23") (pinfunction "GPIO16(ADC1)_B23") (pintype "bidirectional"))
    )
    (net (code "46") (name "Net-(U3-GPIO17(ADC2)-Pad24)") (class "Default")
      (node (ref "U3") (pin "24") (pinfunction "GPIO17(ADC2)_24") (pintype "bidirectional"))
      (node (ref "U3") (pin "B24") (pinfunction "GPIO17(ADC2)_B24") (pintype "bidirectional"))
    )
    (net (code "47") (name "Net-(U3-GPIO19(ADC4)-Pad26)") (class "Default")
      (node (ref "U3") (pin "26") (pinfunction "GPIO19(ADC4)_26") (pintype "bidirectional"))
      (node (ref "U3") (pin "B26") (pinfunction "GPIO19(ADC4)_B26") (pintype "bidirectional"))
    )
    (net (code "48") (name "Net-(U3-GPIO20(ADC5)-Pad27)") (class "Default")
      (node (ref "U3") (pin "27") (pinfunction "GPIO20(ADC5)_27") (pintype "bidirectional"))
      (node (ref "U3") (pin "B27") (pinfunction "GPIO20(ADC5)_B27") (pintype "bidirectional"))
    )
    (net (code "49") (name "Net-(U3-GPIO21(ADC6)-Pad28)") (class "Default")
      (node (ref "U3") (pin "28") (pinfunction "GPIO21(ADC6)_28") (pintype "bidirectional"))
      (node (ref "U3") (pin "B28") (pinfunction "GPIO21(ADC6)_B28") (pintype "bidirectional"))
    )
    (net (code "50") (name "Net-(U3-GPIO25(ADC10)-Pad32)") (class "Default")
      (node (ref "U3") (pin "32") (pinfunction "GPIO25(ADC10)_32") (pintype "bidirectional"))
      (node (ref "U3") (pin "B32") (pinfunction "GPIO25(ADC10)_B32") (pintype "bidirectional"))
    )
    (net (code "51") (name "Net-(U3-GPIO26(SAI2_SD_A)-Pad33)") (class "Default")
      (node (ref "U3") (pin "33") (pinfunction "GPIO26(SAI2_SD_A)_33") (pintype "bidirectional"))
      (node (ref "U3") (pin "B33") (pinfunction "GPIO26(SAI2_SD_A)_B33") (pintype "bidirectional"))
    )
    (net (code "52") (name "Net-(U3-GPIO27(SAI2_FS_B)-Pad34)") (class "Default")
      (node (ref "U3") (pin "34") (pinfunction "GPIO27(SAI2_FS_B)_34") (pintype "bidirectional"))
      (node (ref "U3") (pin "B34") (pinfunction "GPIO27(SAI2_FS_B)_B34") (pintype "bidirectional"))
    )
    (net (code "53") (name "Net-(U4-+3V3_A-Pad21)") (class "Default")
      (node (ref "U4") (pin "21") (pinfunction "+3V3_A_21") (pintype "bidirectional"))
      (node (ref "U4") (pin "B21") (pinfunction "+3V3_A_B21") (pintype "bidirectional"))
    )
    (net (code "54") (name "Net-(U4-AUDIO_IN_L-Pad16)") (class "Default")
      (node (ref "U4") (pin "16") (pinfunction "AUDIO_IN_L_16") (pintype "bidirectional"))
      (node (ref "U4") (pin "B16") (pinfunction "AUDIO_IN_L_B16") (pintype "bidirectional"))
    )
    (net (code "55") (name "Net-(U4-AUDIO_IN_R-Pad17)") (class "Default")
      (node (ref "U4") (pin "17") (pinfunction "AUDIO_IN_R_17") (pintype "bidirectional"))
      (node (ref "U4") (pin "B17") (pinfunction "AUDIO_IN_R_B17") (pintype "bidirectional"))
    )
    (net (code "56") (name "Net-(U4-AUDIO_OUT_R-Pad19)") (class "Default")
      (node (ref "U4") (pin "19") (pinfunction "AUDIO_OUT_R_19") (pintype "bidirectional"))
      (node (ref "U4") (pin "B19") (pinfunction "AUDIO_OUT_R_B19") (pintype "bidirectional"))
    )
    (net (code "57") (name "Net-(U4-GPIO1(SDMMC1_D3)-Pad2)") (class "Default")
      (node (ref "U4") (pin "2") (pinfunction "GPIO1(SDMMC1_D3)_2") (pintype "bidirectional"))
      (node (ref "U4") (pin "B2") (pinfunction "GPIO1(SDMMC1_D3)_B2") (pintype "bidirectional"))
    )
    (net (code "58") (name "Net-(U4-GPIO2(SDMMC1_D2)-Pad3)") (class "Default")
      (node (ref "U4") (pin "3") (pinfunction "GPIO2(SDMMC1_D2)_3") (pintype "bidirectional"))
      (node (ref "U4") (pin "B3") (pinfunction "GPIO2(SDMMC1_D2)_B3") (pintype "bidirectional"))
    )
    (net (code "59") (name "Net-(U4-GPIO3(SDMMC1_D1)-Pad4)") (class "Default")
      (node (ref "U4") (pin "4") (pinfunction "GPIO3(SDMMC1_D1)_4") (pintype "bidirectional"))
      (node (ref "U4") (pin "B4") (pinfunction "GPIO3(SDMMC1_D1)_B4") (pintype "bidirectional"))
    )
    (net (code "60") (name "Net-(U4-GPIO4(SDMMC1_D0)-Pad5)") (class "Default")
      (node (ref "U4") (pin "5") (pinfunction "GPIO4(SDMMC1_D0)_5") (pintype "bidirectional"))
      (node (ref "U4") (pin "B5") (pinfunction "GPIO4(SDMMC1_D0)_B5") (pintype "bidirectional"))
    )
    (net (code "61") (name "Net-(U4-GPIO5(SDMMC1_CMD)-Pad6)") (class "Default")
      (node (ref "U4") (pin "6") (pinfunction "GPIO5(SDMMC1_CMD)_6") (pintype "bidirectional"))
      (node (ref "U4") (pin "B6") (pinfunction "GPIO5(SDMMC1_CMD)_B6") (pintype "bidirectional"))
    )
    (net (code "62") (name "Net-(U4-GPIO6(SDMMC1_CK)-Pad7)") (class "Default")
      (node (ref "U4") (pin "7") (pinfunction "GPIO6(SDMMC1_CK)_7") (pintype "bidirectional"))
      (node (ref "U4") (pin "B7") (pinfunction "GPIO6(SDMMC1_CK)_B7") (pintype "bidirectional"))
    )
    (net (code "63") (name "Net-(U4-GPIO9(SPI1_MISO)-Pad10)") (class "Default")
      (node (ref "U4") (pin "10") (pinfunction "GPIO9(SPI1_MISO)_10") (pintype "bidirectional"))
      (node (ref "U4") (pin "B10") (pinfunction "GPIO9(SPI1_MISO)_B10") (pintype "bidirectional"))
    )
    (net (code "64") (name "Net-(U4-GPIO13(USART1_TX)-Pad14)") (class "Default")
      (node (ref "U4") (pin "14") (pinfunction "GPIO13(USART1_TX)_14") (pintype "bidirectional"))
      (node (ref "U4") (pin "B14") (pinfunction "GPIO13(USART1_TX)_B14") (pintype "bidirectional"))
    )
    (net (code "65") (name "Net-(U4-GPIO14(USART1_RX)-Pad15)") (class "Default")
      (node (ref "U4") (pin "15") (pinfunction "GPIO14(USART1_RX)_15") (pintype "bidirectional"))
      (node (ref "U4") (pin "B15") (pinfunction "GPIO14(USART1_RX)_B15") (pintype "bidirectional"))
    )
    (net (code "66") (name "Net-(U4-GPIO15(ADC0)-Pad22)") (class "Default")
      (node (ref "U4") (pin "22") (pinfunction "GPIO15(ADC0)_22") (pintype "bidirectional"))
      (node (ref "U4") (pin "B22") (pinfunction "GPIO15(ADC0)_B22") (pintype "bidirectional"))
    )
    (net (code "67") (name "Net-(U4-GPIO16(ADC1)-Pad23)") (class "Default")
      (node (ref "U4") (pin "23") (pinfunction "GPIO16(ADC1)_23") (pintype "bidirectional"))
      (node (ref "U4") (pin "B23") (pinfunction "GPIO16(ADC1)_B23") (pintype "bidirectional"))
    )
    (net (code "68") (name "Net-(U4-GPIO17(ADC2)-Pad24)") (class "Default")
      (node (ref "U4") (pin "24") (pinfunction "GPIO17(ADC2)_24") (pintype "bidirectional"))
      (node (ref "U4") (pin "B24") (pinfunction "GPIO17(ADC2)_B24") (pintype "bidirectional"))
    )
    (net (code "69") (name "Net-(U4-GPIO19(ADC4)-Pad26)") (class "Default")
      (node (ref "U4") (pin "26") (pinfunction "GPIO19(ADC4)_26") (pintype "bidirectional"))
      (node (ref "U4") (pin "B26") (pinfunction "GPIO19(ADC4)_B26") (pintype "bidirectional"))
    )
    (net (code "70") (name "Net-(U4-GPIO20(ADC5)-Pad27)") (class "Default")
      (node (ref "U4") (pin "27") (pinfunction "GPIO20(ADC5)_27") (pintype "bidirectional"))
      (node (ref "U4") (pin "B27") (pinfunction "GPIO20(ADC5)_B27") (pintype "bidirectional"))
    )
    (net (code "71") (name "Net-(U4-GPIO21(ADC6)-Pad28)") (class "Default")
      (node (ref "U4") (pin "28") (pinfunction "GPIO21(ADC6)_28") (pintype "bidirectional"))
      (node (ref "U4") (pin "B28") (pinfunction "GPIO21(ADC6)_B28") (pintype "bidirectional"))
    )
    (net (code "72") (name "Net-(U4-GPIO24(ADC9)-Pad31)") (class "Default")
      (node (ref "U4") (pin "31") (pinfunction "GPIO24(ADC9)_31") (pintype "bidirectional"))
      (node (ref "U4") (pin "B31") (pinfunction "GPIO24(ADC9)_B31") (pintype "bidirectional"))
    )
    (net (code "73") (name "Net-(U4-GPIO25(ADC10)-Pad32)") (class "Default")
      (node (ref "U4") (pin "32") (pinfunction "GPIO25(ADC10)_32") (pintype "bidirectional"))
      (node (ref "U4") (pin "B32") (pinfunction "GPIO25(ADC10)_B32") (pintype "bidirectional"))
    )
    (net (code "74") (name "Net-(U4-GPIO26(SAI2_SD_A)-Pad33)") (class "Default")
      (node (ref "U4") (pin "33") (pinfunction "GPIO26(SAI2_SD_A)_33") (pintype "bidirectional"))
      (node (ref "U4") (pin "B33") (pinfunction "GPIO26(SAI2_SD_A)_B33") (pintype "bidirectional"))
    )
    (net (code "75") (name "Net-(U4-GPIO27(SAI2_FS_B)-Pad34)") (class "Default")
      (node (ref "U4") (pin "34") (pinfunction "GPIO27(SAI2_FS_B)_34") (pintype "bidirectional"))
      (node (ref "U4") (pin "B34") (pinfunction "GPIO27(SAI2_FS_B)_B34") (pintype "bidirectional"))
    )
    (net (code "76") (name "Net-(U5-+3V3_A-Pad21)") (class "Default")
      (node (ref "U5") (pin "21") (pinfunction "+3V3_A_21") (pintype "bidirectional"))
      (node (ref "U5") (pin "B21") (pinfunction "+3V3_A_B21") (pintype "bidirectional"))
    )
    (net (code "77") (name "Net-(U5-AUDIO_IN_L-Pad16)") (class "Default")
      (node (ref "U5") (pin "16") (pinfunction "AUDIO_IN_L_16") (pintype "bidirectional"))
      (node (ref "U5") (pin "B16") (pinfunction "AUDIO_IN_L_B16") (pintype "bidirectional"))
    )
    (net (code "78") (name "Net-(U5-AUDIO_IN_R-Pad17)") (class "Default")
      (node (ref "U5") (pin "17") (pinfunction "AUDIO_IN_R_17") (pintype "bidirectional"))
      (node (ref "U5") (pin "B17") (pinfunction "AUDIO_IN_R_B17") (pintype "bidirectional"))
    )
    (net (code "79") (name "Net-(U5-AUDIO_OUT_R-Pad19)") (class "Default")
      (node (ref "U5") (pin "19") (pinfunction "AUDIO_OUT_R_19") (pintype "bidirectional"))
      (node (ref "U5") (pin "B19") (pinfunction "AUDIO_OUT_R_B19") (pintype "bidirectional"))
    )
    (net (code "80") (name "Net-(U5-GPIO1(SDMMC1_D3)-Pad2)") (class "Default")
      (node (ref "U5") (pin "2") (pinfunction "GPIO1(SDMMC1_D3)_2") (pintype "bidirectional"))
      (node (ref "U5") (pin "B2") (pinfunction "GPIO1(SDMMC1_D3)_B2") (pintype "bidirectional"))
    )
    (net (code "81") (name "Net-(U5-GPIO2(SDMMC1_D2)-Pad3)") (class "Default")
      (node (ref "U5") (pin "3") (pinfunction "GPIO2(SDMMC1_D2)_3") (pintype "bidirectional"))
      (node (ref "U5") (pin "B3") (pinfunction "GPIO2(SDMMC1_D2)_B3") (pintype "bidirectional"))
    )
    (net (code "82") (name "Net-(U5-GPIO3(SDMMC1_D1)-Pad4)") (class "Default")
      (node (ref "U5") (pin "4") (pinfunction "GPIO3(SDMMC1_D1)_4") (pintype "bidirectional"))
      (node (ref "U5") (pin "B4") (pinfunction "GPIO3(SDMMC1_D1)_B4") (pintype "bidirectional"))
    )
    (net (code "83") (name "Net-(U5-GPIO4(SDMMC1_D0)-Pad5)") (class "Default")
      (node (ref "U5") (pin "5") (pinfunction "GPIO4(SDMMC1_D0)_5") (pintype "bidirectional"))
      (node (ref "U5") (pin "B5") (pinfunction "GPIO4(SDMMC1_D0)_B5") (pintype "bidirectional"))
    )
    (net (code "84") (name "Net-(U5-GPIO5(SDMMC1_CMD)-Pad6)") (class "Default")
      (node (ref "U5") (pin "6") (pinfunction "GPIO5(SDMMC1_CMD)_6") (pintype "bidirectional"))
      (node (ref "U5") (pin "B6") (pinfunction "GPIO5(SDMMC1_CMD)_B6") (pintype "bidirectional"))
    )
    (net (code "85") (name "Net-(U5-GPIO6(SDMMC1_CK)-Pad7)") (class "Default")
      (node (ref "U5") (pin "7") (pinfunction "GPIO6(SDMMC1_CK)_7") (pintype "bidirectional"))
      (node (ref "U5") (pin "B7") (pinfunction "GPIO6(SDMMC1_CK)_B7") (pintype "bidirectional"))
    )
    (net (code "86") (name "Net-(U5-GPIO9(SPI1_MISO)-Pad10)") (class "Default")
      (node (ref "U5") (pin "10") (pinfunction "GPIO9(SPI1_MISO)_10") (pintype "bidirectional"))
      (node (ref "U5") (pin "B10") (pinfunction "GPIO9(SPI1_MISO)_B10") (pintype "bidirectional"))
    )
    (net (code "87") (name "Net-(U5-GPIO13(USART1_TX)-Pad14)") (class "Default")
      (node (ref "U5") (pin "14") (pinfunction "GPIO13(USART1_TX)_14") (pintype "bidirectional"))
      (node (ref "U5") (pin "B14") (pinfunction "GPIO13(USART1_TX)_B14") (pintype "bidirectional"))
    )
    (net (code "88") (name "Net-(U5-GPIO14(USART1_RX)-Pad15)") (class "Default")
      (node (ref "U5") (pin "15") (pinfunction "GPIO14(USART1_RX)_15") (pintype "bidirectional"))
      (node (ref "U5") (pin "B15") (pinfunction "GPIO14(USART1_RX)_B15") (pintype "bidirectional"))
    )
    (net (code "89") (name "Net-(U5-GPIO15(ADC0)-Pad22)") (class "Default")
      (node (ref "U5") (pin "22") (pinfunction "GPIO15(ADC0)_22") (pintype "bidirectional"))
      (node (ref "U5") (pin "B22") (pinfunction "GPIO15(ADC0)_B22") (pintype "bidirectional"))
    )
    (net (code "90") (name "Net-(U5-GPIO16(ADC1)-Pad23)") (class "Default")
      (node (ref "U5") (pin "23") (pinfunction "GPIO16(ADC1)_23") (pintype "bidirectional"))
      (node (ref "U5") (pin "B23") (pinfunction "GPIO16(ADC1)_B23") (pintype "bidirectional"))
    )
    (net (code "91") (name "Net-(U5-GPIO17(ADC2)-Pad24)") (class "Default")
      (node (ref "U5") (pin "24") (pinfunction "GPIO17(ADC2)_24") (pintype "bidirectional"))
      (node (ref "U5") (pin "B24") (pinfunction "GPIO17(ADC2)_B24") (pintype "bidirectional"))
    )
    (net (code "92") (name "Net-(U5-GPIO19(ADC4)-Pad26)") (class "Default")
      (node (ref "U5") (pin "26") (pinfunction "GPIO19(ADC4)_26") (pintype "bidirectional"))
      (node (ref "U5") (pin "B26") (pinfunction "GPIO19(ADC4)_B26") (pintype "bidirectional"))
    )
    (net (code "93") (name "Net-(U5-GPIO20(ADC5)-Pad27)") (class "Default")
      (node (ref "U5") (pin "27") (pinfunction "GPIO20(ADC5)_27") (pintype "bidirectional"))
      (node (ref "U5") (pin "B27") (pinfunction "GPIO20(ADC5)_B27") (pintype "bidirectional"))
    )
    (net (code "94") (name "Net-(U5-GPIO21(ADC6)-Pad28)") (class "Default")
      (node (ref "U5") (pin "28") (pinfunction "GPIO21(ADC6)_28") (pintype "bidirectional"))
      (node (ref "U5") (pin "B28") (pinfunction "GPIO21(ADC6)_B28") (pintype "bidirectional"))
    )
    (net (code "95") (name "Net-(U5-GPIO24(ADC9)-Pad31)") (class "Default")
      (node (ref "U5") (pin "31") (pinfunction "GPIO24(ADC9)_31") (pintype "bidirectional"))
      (node (ref "U5") (pin "B31") (pinfunction "GPIO24(ADC9)_B31") (pintype "bidirectional"))
    )
    (net (code "96") (name "Net-(U5-GPIO25(ADC10)-Pad32)") (class "Default")
      (node (ref "U5") (pin "32") (pinfunction "GPIO25(ADC10)_32") (pintype "bidirectional"))
      (node (ref "U5") (pin "B32") (pinfunction "GPIO25(ADC10)_B32") (pintype "bidirectional"))
    )
    (net (code "97") (name "Net-(U5-GPIO26(SAI2_SD_A)-Pad33)") (class "Default")
      (node (ref "U5") (pin "33") (pinfunction "GPIO26(SAI2_SD_A)_33") (pintype "bidirectional"))
      (node (ref "U5") (pin "B33") (pinfunction "GPIO26(SAI2_SD_A)_B33") (pintype "bidirectional"))
    )
    (net (code "98") (name "Net-(U5-GPIO27(SAI2_FS_B)-Pad34)") (class "Default")
      (node (ref "U5") (pin "34") (pinfunction "GPIO27(SAI2_FS_B)_34") (pintype "bidirectional"))
      (node (ref "U5") (pin "B34") (pinfunction "GPIO27(SAI2_FS_B)_B34") (pintype "bidirectional"))
    )
    (net (code "99") (name "Net-(U6-+3V3_A-Pad21)") (class "Default")
      (node (ref "U6") (pin "21") (pinfunction "+3V3_A_21") (pintype "bidirectional"))
      (node (ref "U6") (pin "B21") (pinfunction "+3V3_A_B21") (pintype "bidirectional"))
    )
    (net (code "100") (name "Net-(U6-+3V3_D-Pad38)") (class "Default")
      (node (ref "U6") (pin "37") (pinfunction "GPIO30(USB_HS_D+)_37") (pintype "bidirectional"))
      (node (ref "U6") (pin "38") (pinfunction "+3V3_D_38") (pintype "bidirectional"))
      (node (ref "U6") (pin "B37") (pinfunction "GPIO30(USB_HS_D+)_B37") (pintype "bidirectional"))
      (node (ref "U6") (pin "B38") (pinfunction "+3V3_D_B38") (pintype "bidirectional"))
    )
    (net (code "101") (name "Net-(U6-AUDIO_IN_L-Pad16)") (class "Default")
      (node (ref "U6") (pin "16") (pinfunction "AUDIO_IN_L_16") (pintype "bidirectional"))
      (node (ref "U6") (pin "B16") (pinfunction "AUDIO_IN_L_B16") (pintype "bidirectional"))
    )
    (net (code "102") (name "Net-(U6-AUDIO_IN_R-Pad17)") (class "Default")
      (node (ref "U6") (pin "17") (pinfunction "AUDIO_IN_R_17") (pintype "bidirectional"))
      (node (ref "U6") (pin "B17") (pinfunction "AUDIO_IN_R_B17") (pintype "bidirectional"))
    )
    (net (code "103") (name "Net-(U6-AUDIO_OUT_R-Pad19)") (class "Default")
      (node (ref "U6") (pin "19") (pinfunction "AUDIO_OUT_R_19") (pintype "bidirectional"))
      (node (ref "U6") (pin "B19") (pinfunction "AUDIO_OUT_R_B19") (pintype "bidirectional"))
    )
    (net (code "104") (name "Net-(U6-GPIO1(SDMMC1_D3)-Pad2)") (class "Default")
      (node (ref "U6") (pin "2") (pinfunction "GPIO1(SDMMC1_D3)_2") (pintype "bidirectional"))
      (node (ref "U6") (pin "B2") (pinfunction "GPIO1(SDMMC1_D3)_B2") (pintype "bidirectional"))
    )
    (net (code "105") (name "Net-(U6-GPIO2(SDMMC1_D2)-Pad3)") (class "Default")
      (node (ref "U6") (pin "3") (pinfunction "GPIO2(SDMMC1_D2)_3") (pintype "bidirectional"))
      (node (ref "U6") (pin "B3") (pinfunction "GPIO2(SDMMC1_D2)_B3") (pintype "bidirectional"))
    )
    (net (code "106") (name "Net-(U6-GPIO3(SDMMC1_D1)-Pad4)") (class "Default")
      (node (ref "U6") (pin "4") (pinfunction "GPIO3(SDMMC1_D1)_4") (pintype "bidirectional"))
      (node (ref "U6") (pin "B4") (pinfunction "GPIO3(SDMMC1_D1)_B4") (pintype "bidirectional"))
    )
    (net (code "107") (name "Net-(U6-GPIO4(SDMMC1_D0)-Pad5)") (class "Default")
      (node (ref "U6") (pin "5") (pinfunction "GPIO4(SDMMC1_D0)_5") (pintype "bidirectional"))
      (node (ref "U6") (pin "B5") (pinfunction "GPIO4(SDMMC1_D0)_B5") (pintype "bidirectional"))
    )
    (net (code "108") (name "Net-(U6-GPIO5(SDMMC1_CMD)-Pad6)") (class "Default")
      (node (ref "U6") (pin "6") (pinfunction "GPIO5(SDMMC1_CMD)_6") (pintype "bidirectional"))
      (node (ref "U6") (pin "B6") (pinfunction "GPIO5(SDMMC1_CMD)_B6") (pintype "bidirectional"))
    )
    (net (code "109") (name "Net-(U6-GPIO6(SDMMC1_CK)-Pad7)") (class "Default")
      (node (ref "U6") (pin "7") (pinfunction "GPIO6(SDMMC1_CK)_7") (pintype "bidirectional"))
      (node (ref "U6") (pin "B7") (pinfunction "GPIO6(SDMMC1_CK)_B7") (pintype "bidirectional"))
    )
    (net (code "110") (name "Net-(U6-GPIO9(SPI1_MISO)-Pad10)") (class "Default")
      (node (ref "U6") (pin "10") (pinfunction "GPIO9(SPI1_MISO)_10") (pintype "bidirectional"))
      (node (ref "U6") (pin "B10") (pinfunction "GPIO9(SPI1_MISO)_B10") (pintype "bidirectional"))
    )
    (net (code "111") (name "Net-(U6-GPIO13(USART1_TX)-Pad14)") (class "Default")
      (node (ref "U6") (pin "14") (pinfunction "GPIO13(USART1_TX)_14") (pintype "bidirectional"))
      (node (ref "U6") (pin "B14") (pinfunction "GPIO13(USART1_TX)_B14") (pintype "bidirectional"))
    )
    (net (code "112") (name "Net-(U6-GPIO14(USART1_RX)-Pad15)") (class "Default")
      (node (ref "U6") (pin "15") (pinfunction "GPIO14(USART1_RX)_15") (pintype "bidirectional"))
      (node (ref "U6") (pin "B15") (pinfunction "GPIO14(USART1_RX)_B15") (pintype "bidirectional"))
    )
    (net (code "113") (name "Net-(U6-GPIO15(ADC0)-Pad22)") (class "Default")
      (node (ref "U6") (pin "22") (pinfunction "GPIO15(ADC0)_22") (pintype "bidirectional"))
      (node (ref "U6") (pin "B22") (pinfunction "GPIO15(ADC0)_B22") (pintype "bidirectional"))
    )
    (net (code "114") (name "Net-(U6-GPIO16(ADC1)-Pad23)") (class "Default")
      (node (ref "U6") (pin "23") (pinfunction "GPIO16(ADC1)_23") (pintype "bidirectional"))
      (node (ref "U6") (pin "B23") (pinfunction "GPIO16(ADC1)_B23") (pintype "bidirectional"))
    )
    (net (code "115") (name "Net-(U6-GPIO17(ADC2)-Pad24)") (class "Default")
      (node (ref "U6") (pin "24") (pinfunction "GPIO17(ADC2)_24") (pintype "bidirectional"))
      (node (ref "U6") (pin "B24") (pinfunction "GPIO17(ADC2)_B24") (pintype "bidirectional"))
    )
    (net (code "116") (name "Net-(U6-GPIO19(ADC4)-Pad26)") (class "Default")
      (node (ref "U6") (pin "26") (pinfunction "GPIO19(ADC4)_26") (pintype "bidirectional"))
      (node (ref "U6") (pin "B26") (pinfunction "GPIO19(ADC4)_B26") (pintype "bidirectional"))
    )
    (net (code "117") (name "Net-(U6-GPIO20(ADC5)-Pad27)") (class "Default")
      (node (ref "U6") (pin "27") (pinfunction "GPIO20(ADC5)_27") (pintype "bidirectional"))
      (node (ref "U6") (pin "B27") (pinfunction "GPIO20(ADC5)_B27") (pintype "bidirectional"))
    )
    (net (code "118") (name "Net-(U6-GPIO21(ADC6)-Pad28)") (class "Default")
      (node (ref "U6") (pin "28") (pinfunction "GPIO21(ADC6)_28") (pintype "bidirectional"))
      (node (ref "U6") (pin "B28") (pinfunction "GPIO21(ADC6)_B28") (pintype "bidirectional"))
    )
    (net (code "119") (name "Net-(U6-GPIO24(ADC9)-Pad31)") (class "Default")
      (node (ref "U6") (pin "31") (pinfunction "GPIO24(ADC9)_31") (pintype "bidirectional"))
      (node (ref "U6") (pin "B31") (pinfunction "GPIO24(ADC9)_B31") (pintype "bidirectional"))
    )
    (net (code "120") (name "Net-(U6-GPIO25(ADC10)-Pad32)") (class "Default")
      (node (ref "U6") (pin "32") (pinfunction "GPIO25(ADC10)_32") (pintype "bidirectional"))
      (node (ref "U6") (pin "B32") (pinfunction "GPIO25(ADC10)_B32") (pintype "bidirectional"))
    )
    (net (code "121") (name "Net-(U6-GPIO26(SAI2_SD_A)-Pad33)") (class "Default")
      (node (ref "U6") (pin "33") (pinfunction "GPIO26(SAI2_SD_A)_33") (pintype "bidirectional"))
      (node (ref "U6") (pin "B33") (pinfunction "GPIO26(SAI2_SD_A)_B33") (pintype "bidirectional"))
    )
    (net (code "122") (name "Net-(U6-GPIO27(SAI2_FS_B)-Pad34)") (class "Default")
      (node (ref "U6") (pin "34") (pinfunction "GPIO27(SAI2_FS_B)_34") (pintype "bidirectional"))
      (node (ref "U6") (pin "B34") (pinfunction "GPIO27(SAI2_FS_B)_B34") (pintype "bidirectional"))
    )
    (net (code "123") (name "Net-(U7-+3V3_A-Pad21)") (class "Default")
      (node (ref "U7") (pin "21") (pinfunction "+3V3_A_21") (pintype "bidirectional"))
      (node (ref "U7") (pin "B21") (pinfunction "+3V3_A_B21") (pintype "bidirectional"))
    )
    (net (code "124") (name "Net-(U7-AUDIO_IN_L-Pad16)") (class "Default")
      (node (ref "U7") (pin "16") (pinfunction "AUDIO_IN_L_16") (pintype "bidirectional"))
      (node (ref "U7") (pin "B16") (pinfunction "AUDIO_IN_L_B16") (pintype "bidirectional"))
    )
    (net (code "125") (name "Net-(U7-AUDIO_IN_R-Pad17)") (class "Default")
      (node (ref "U7") (pin "17") (pinfunction "AUDIO_IN_R_17") (pintype "bidirectional"))
      (node (ref "U7") (pin "B17") (pinfunction "AUDIO_IN_R_B17") (pintype "bidirectional"))
    )
    (net (code "126") (name "Net-(U7-AUDIO_OUT_R-Pad19)") (class "Default")
      (node (ref "U7") (pin "19") (pinfunction "AUDIO_OUT_R_19") (pintype "bidirectional"))
      (node (ref "U7") (pin "B19") (pinfunction "AUDIO_OUT_R_B19") (pintype "bidirectional"))
    )
    (net (code "127") (name "Net-(U7-GPIO14(USART1_RX)-Pad15)") (class "Default")
      (node (ref "U7") (pin "15") (pinfunction "GPIO14(USART1_RX)_15") (pintype "bidirectional"))
      (node (ref "U7") (pin "B15") (pinfunction "GPIO14(USART1_RX)_B15") (pintype "bidirectional"))
    )
    (net (code "128") (name "Net-(U7-GPIO15(ADC0)-Pad22)") (class "Default")
      (node (ref "U7") (pin "22") (pinfunction "GPIO15(ADC0)_22") (pintype "bidirectional"))
      (node (ref "U7") (pin "B22") (pinfunction "GPIO15(ADC0)_B22") (pintype "bidirectional"))
    )
    (net (code "129") (name "Net-(U7-GPIO16(ADC1)-Pad23)") (class "Default")
      (node (ref "U7") (pin "23") (pinfunction "GPIO16(ADC1)_23") (pintype "bidirectional"))
      (node (ref "U7") (pin "B23") (pinfunction "GPIO16(ADC1)_B23") (pintype "bidirectional"))
    )
    (net (code "130") (name "Net-(U7-GPIO17(ADC2)-Pad24)") (class "Default")
      (node (ref "U7") (pin "24") (pinfunction "GPIO17(ADC2)_24") (pintype "bidirectional"))
      (node (ref "U7") (pin "B24") (pinfunction "GPIO17(ADC2)_B24") (pintype "bidirectional"))
    )
    (net (code "131") (name "Net-(U7-GPIO19(ADC4)-Pad26)") (class "Default")
      (node (ref "U7") (pin "26") (pinfunction "GPIO19(ADC4)_26") (pintype "bidirectional"))
      (node (ref "U7") (pin "B26") (pinfunction "GPIO19(ADC4)_B26") (pintype "bidirectional"))
    )
    (net (code "132") (name "Net-(U7-GPIO20(ADC5)-Pad27)") (class "Default")
      (node (ref "U7") (pin "27") (pinfunction "GPIO20(ADC5)_27") (pintype "bidirectional"))
      (node (ref "U7") (pin "B27") (pinfunction "GPIO20(ADC5)_B27") (pintype "bidirectional"))
    )
    (net (code "133") (name "Net-(U7-GPIO21(ADC6)-Pad28)") (class "Default")
      (node (ref "U7") (pin "28") (pinfunction "GPIO21(ADC6)_28") (pintype "bidirectional"))
      (node (ref "U7") (pin "B28") (pinfunction "GPIO21(ADC6)_B28") (pintype "bidirectional"))
    )
    (net (code "134") (name "Net-(U7-GPIO25(ADC10)-Pad32)") (class "Default")
      (node (ref "U7") (pin "32") (pinfunction "GPIO25(ADC10)_32") (pintype "bidirectional"))
      (node (ref "U7") (pin "B32") (pinfunction "GPIO25(ADC10)_B32") (pintype "bidirectional"))
    )
    (net (code "135") (name "Net-(U7-GPIO26(SAI2_SD_A)-Pad33)") (class "Default")
      (node (ref "U7") (pin "33") (pinfunction "GPIO26(SAI2_SD_A)_33") (pintype "bidirectional"))
      (node (ref "U7") (pin "B33") (pinfunction "GPIO26(SAI2_SD_A)_B33") (pintype "bidirectional"))
    )
    (net (code "136") (name "Net-(U7-GPIO27(SAI2_FS_B)-Pad34)") (class "Default")
      (node (ref "U7") (pin "34") (pinfunction "GPIO27(SAI2_FS_B)_34") (pintype "bidirectional"))
      (node (ref "U7") (pin "B34") (pinfunction "GPIO27(SAI2_FS_B)_B34") (pintype "bidirectional"))
    )
    (net (code "137") (name "Net-(U8-+3V3_A-Pad21)") (class "Default")
      (node (ref "U8") (pin "21") (pinfunction "+3V3_A_21") (pintype "bidirectional"))
      (node (ref "U8") (pin "B21") (pinfunction "+3V3_A_B21") (pintype "bidirectional"))
    )
    (net (code "138") (name "Net-(U8-+3V3_D-Pad38)") (class "Default")
      (node (ref "U8") (pin "35") (pinfunction "GPIO28(ADC11)_35") (pintype "bidirectional"))
      (node (ref "U8") (pin "37") (pinfunction "GPIO30(USB_HS_D+)_37") (pintype "bidirectional"))
      (node (ref "U8") (pin "38") (pinfunction "+3V3_D_38") (pintype "bidirectional"))
      (node (ref "U8") (pin "B35") (pinfunction "GPIO28(ADC11)_B35") (pintype "bidirectional"))
      (node (ref "U8") (pin "B37") (pinfunction "GPIO30(USB_HS_D+)_B37") (pintype "bidirectional"))
      (node (ref "U8") (pin "B38") (pinfunction "+3V3_D_B38") (pintype "bidirectional"))
    )
    (net (code "139") (name "Net-(U8-AUDIO_IN_L-Pad16)") (class "Default")
      (node (ref "U8") (pin "16") (pinfunction "AUDIO_IN_L_16") (pintype "bidirectional"))
      (node (ref "U8") (pin "B16") (pinfunction "AUDIO_IN_L_B16") (pintype "bidirectional"))
    )
    (net (code "140") (name "Net-(U8-AUDIO_IN_R-Pad17)") (class "Default")
      (node (ref "U8") (pin "17") (pinfunction "AUDIO_IN_R_17") (pintype "bidirectional"))
      (node (ref "U8") (pin "B17") (pinfunction "AUDIO_IN_R_B17") (pintype "bidirectional"))
    )
    (net (code "141") (name "Net-(U8-AUDIO_OUT_R-Pad19)") (class "Default")
      (node (ref "U8") (pin "19") (pinfunction "AUDIO_OUT_R_19") (pintype "bidirectional"))
      (node (ref "U8") (pin "B19") (pinfunction "AUDIO_OUT_R_B19") (pintype "bidirectional"))
    )
    (net (code "142") (name "Net-(U8-GPIO1(SDMMC1_D3)-Pad2)") (class "Default")
      (node (ref "U8") (pin "2") (pinfunction "GPIO1(SDMMC1_D3)_2") (pintype "bidirectional"))
      (node (ref "U8") (pin "B2") (pinfunction "GPIO1(SDMMC1_D3)_B2") (pintype "bidirectional"))
    )
    (net (code "143") (name "Net-(U8-GPIO2(SDMMC1_D2)-Pad3)") (class "Default")
      (node (ref "U8") (pin "3") (pinfunction "GPIO2(SDMMC1_D2)_3") (pintype "bidirectional"))
      (node (ref "U8") (pin "B3") (pinfunction "GPIO2(SDMMC1_D2)_B3") (pintype "bidirectional"))
    )
    (net (code "144") (name "Net-(U8-GPIO3(SDMMC1_D1)-Pad4)") (class "Default")
      (node (ref "U8") (pin "4") (pinfunction "GPIO3(SDMMC1_D1)_4") (pintype "bidirectional"))
      (node (ref "U8") (pin "B4") (pinfunction "GPIO3(SDMMC1_D1)_B4") (pintype "bidirectional"))
    )
    (net (code "145") (name "Net-(U8-GPIO4(SDMMC1_D0)-Pad5)") (class "Default")
      (node (ref "U8") (pin "5") (pinfunction "GPIO4(SDMMC1_D0)_5") (pintype "bidirectional"))
      (node (ref "U8") (pin "B5") (pinfunction "GPIO4(SDMMC1_D0)_B5") (pintype "bidirectional"))
    )
    (net (code "146") (name "Net-(U8-GPIO5(SDMMC1_CMD)-Pad6)") (class "Default")
      (node (ref "U8") (pin "6") (pinfunction "GPIO5(SDMMC1_CMD)_6") (pintype "bidirectional"))
      (node (ref "U8") (pin "B6") (pinfunction "GPIO5(SDMMC1_CMD)_B6") (pintype "bidirectional"))
    )
    (net (code "147") (name "Net-(U8-GPIO6(SDMMC1_CK)-Pad7)") (class "Default")
      (node (ref "U8") (pin "7") (pinfunction "GPIO6(SDMMC1_CK)_7") (pintype "bidirectional"))
      (node (ref "U8") (pin "B7") (pinfunction "GPIO6(SDMMC1_CK)_B7") (pintype "bidirectional"))
    )
    (net (code "148") (name "Net-(U8-GPIO9(SPI1_MISO)-Pad10)") (class "Default")
      (node (ref "U8") (pin "10") (pinfunction "GPIO9(SPI1_MISO)_10") (pintype "bidirectional"))
      (node (ref "U8") (pin "B10") (pinfunction "GPIO9(SPI1_MISO)_B10") (pintype "bidirectional"))
    )
    (net (code "149") (name "Net-(U8-GPIO13(USART1_TX)-Pad14)") (class "Default")
      (node (ref "U8") (pin "14") (pinfunction "GPIO13(USART1_TX)_14") (pintype "bidirectional"))
      (node (ref "U8") (pin "B14") (pinfunction "GPIO13(USART1_TX)_B14") (pintype "bidirectional"))
    )
    (net (code "150") (name "Net-(U8-GPIO14(USART1_RX)-Pad15)") (class "Default")
      (node (ref "U8") (pin "15") (pinfunction "GPIO14(USART1_RX)_15") (pintype "bidirectional"))
      (node (ref "U8") (pin "B15") (pinfunction "GPIO14(USART1_RX)_B15") (pintype "bidirectional"))
    )
    (net (code "151") (name "Net-(U8-GPIO15(ADC0)-Pad22)") (class "Default")
      (node (ref "U8") (pin "22") (pinfunction "GPIO15(ADC0)_22") (pintype "bidirectional"))
      (node (ref "U8") (pin "B22") (pinfunction "GPIO15(ADC0)_B22") (pintype "bidirectional"))
    )
    (net (code "152") (name "Net-(U8-GPIO16(ADC1)-Pad23)") (class "Default")
      (node (ref "U8") (pin "23") (pinfunction "GPIO16(ADC1)_23") (pintype "bidirectional"))
      (node (ref "U8") (pin "B23") (pinfunction "GPIO16(ADC1)_B23") (pintype "bidirectional"))
    )
    (net (code "153") (name "Net-(U8-GPIO17(ADC2)-Pad24)") (class "Default")
      (node (ref "U8") (pin "24") (pinfunction "GPIO17(ADC2)_24") (pintype "bidirectional"))
      (node (ref "U8") (pin "B24") (pinfunction "GPIO17(ADC2)_B24") (pintype "bidirectional"))
    )
    (net (code "154") (name "Net-(U8-GPIO19(ADC4)-Pad26)") (class "Default")
      (node (ref "U8") (pin "26") (pinfunction "GPIO19(ADC4)_26") (pintype "bidirectional"))
      (node (ref "U8") (pin "B26") (pinfunction "GPIO19(ADC4)_B26") (pintype "bidirectional"))
    )
    (net (code "155") (name "Net-(U8-GPIO20(ADC5)-Pad27)") (class "Default")
      (node (ref "U8") (pin "27") (pinfunction "GPIO20(ADC5)_27") (pintype "bidirectional"))
      (node (ref "U8") (pin "B27") (pinfunction "GPIO20(ADC5)_B27") (pintype "bidirectional"))
    )
    (net (code "156") (name "Net-(U8-GPIO21(ADC6)-Pad28)") (class "Default")
      (node (ref "U8") (pin "28") (pinfunction "GPIO21(ADC6)_28") (pintype "bidirectional"))
      (node (ref "U8") (pin "B28") (pinfunction "GPIO21(ADC6)_B28") (pintype "bidirectional"))
    )
    (net (code "157") (name "Net-(U8-GPIO24(ADC9)-Pad31)") (class "Default")
      (node (ref "U8") (pin "31") (pinfunction "GPIO24(ADC9)_31") (pintype "bidirectional"))
      (node (ref "U8") (pin "B31") (pinfunction "GPIO24(ADC9)_B31") (pintype "bidirectional"))
    )
    (net (code "158") (name "Net-(U8-GPIO25(ADC10)-Pad32)") (class "Default")
      (node (ref "U8") (pin "32") (pinfunction "GPIO25(ADC10)_32") (pintype "bidirectional"))
      (node (ref "U8") (pin "B32") (pinfunction "GPIO25(ADC10)_B32") (pintype "bidirectional"))
    )
    (net (code "159") (name "Net-(U8-GPIO26(SAI2_SD_A)-Pad33)") (class "Default")
      (node (ref "U8") (pin "33") (pinfunction "GPIO26(SAI2_SD_A)_33") (pintype "bidirectional"))
      (node (ref "U8") (pin "B33") (pinfunction "GPIO26(SAI2_SD_A)_B33") (pintype "bidirectional"))
    )
    (net (code "160") (name "Net-(U8-GPIO27(SAI2_FS_B)-Pad34)") (class "Default")
      (node (ref "U8") (pin "34") (pinfunction "GPIO27(SAI2_FS_B)_34") (pintype "bidirectional"))
      (node (ref "U8") (pin "B34") (pinfunction "GPIO27(SAI2_FS_B)_B34") (pintype "bidirectional"))
    )
    (net (code "161") (name "Net-(X1C-KL)") (class "Default")
      (node (ref "R27") (pin "2") (pinfunction "2_2") (pintype "passive"))
      (node (ref "X1") (pin "11") (pinfunction "KL_11") (pintype "passive"))
    )
    (net (code "162") (name "OUT1") (class "Default")
      (node (ref "C25") (pin "1") (pinfunction "1_1") (pintype "passive"))
      (node (ref "U7") (pin "18") (pinfunction "AUDIO_OUT_L_18") (pintype "bidirectional"))
      (node (ref "U7") (pin "B18") (pinfunction "AUDIO_OUT_L_B18") (pintype "bidirectional"))
    )
    (net (code "163") (name "OUT2") (class "Default")
      (node (ref "C21") (pin "1") (pinfunction "1_1") (pintype "passive"))
      (node (ref "U3") (pin "18") (pinfunction "AUDIO_OUT_L_18") (pintype "bidirectional"))
      (node (ref "U3") (pin "B18") (pinfunction "AUDIO_OUT_L_B18") (pintype "bidirectional"))
    )
    (net (code "164") (name "OUT3") (class "Default")
      (node (ref "C26") (pin "1") (pinfunction "1_1") (pintype "passive"))
      (node (ref "U4") (pin "18") (pinfunction "AUDIO_OUT_L_18") (pintype "bidirectional"))
      (node (ref "U4") (pin "B18") (pinfunction "AUDIO_OUT_L_B18") (pintype "bidirectional"))
    )
    (net (code "165") (name "OUT4") (class "Default")
      (node (ref "C27") (pin "1") (pinfunction "1_1") (pintype "passive"))
      (node (ref "U5") (pin "18") (pinfunction "AUDIO_OUT_L_18") (pintype "bidirectional"))
      (node (ref "U5") (pin "B18") (pinfunction "AUDIO_OUT_L_B18") (pintype "bidirectional"))
    )
    (net (code "166") (name "OUT5") (class "Default")
      (node (ref "C29") (pin "1") (pinfunction "1_1") (pintype "passive"))
      (node (ref "U6") (pin "18") (pinfunction "AUDIO_OUT_L_18") (pintype "bidirectional"))
      (node (ref "U6") (pin "B18") (pinfunction "AUDIO_OUT_L_B18") (pintype "bidirectional"))
    )
    (net (code "167") (name "OUT6") (class "Default")
      (node (ref "C31") (pin "1") (pinfunction "1_1") (pintype "passive"))
      (node (ref "U8") (pin "18") (pinfunction "AUDIO_OUT_L_18") (pintype "bidirectional"))
      (node (ref "U8") (pin "B18") (pinfunction "AUDIO_OUT_L_B18") (pintype "bidirectional"))
    )
    (net (code "168") (name "PA1_SD_DETECT") (class "Default")
      (node (ref "J2") (pin "9") (pinfunction "DET_9") (pintype "bidirectional"))
      (node (ref "U3") (pin "31") (pinfunction "GPIO24(ADC9)_31") (pintype "bidirectional"))
      (node (ref "U3") (pin "B31") (pinfunction "GPIO24(ADC9)_B31") (pintype "bidirectional"))
      (node (ref "U7") (pin "31") (pinfunction "GPIO24(ADC9)_31") (pintype "bidirectional"))
      (node (ref "U7") (pin "B31") (pinfunction "GPIO24(ADC9)_B31") (pintype "bidirectional"))
    )
    (net (code "169") (name "PULLUPED") (class "Default")
      (node (ref "U5") (pin "35") (pinfunction "GPIO28(ADC11)_35") (pintype "bidirectional"))
      (node (ref "U5") (pin "36") (pinfunction "GPIO29(USB_HS_D_-)_36") (pintype "bidirectional"))
      (node (ref "U5") (pin "38") (pinfunction "+3V3_D_38") (pintype "bidirectional"))
      (node (ref "U5") (pin "B35") (pinfunction "GPIO28(ADC11)_B35") (pintype "bidirectional"))
      (node (ref "U5") (pin "B36") (pinfunction "GPIO29(USB_HS_D_-)_B36") (pintype "bidirectional"))
      (node (ref "U5") (pin "B38") (pinfunction "+3V3_D_B38") (pintype "bidirectional"))
    )
    (net (code "170") (name "PULLUPED2") (class "Default")
      (node (ref "U4") (pin "36") (pinfunction "GPIO29(USB_HS_D_-)_36") (pintype "bidirectional"))
      (node (ref "U4") (pin "38") (pinfunction "+3V3_D_38") (pintype "bidirectional"))
      (node (ref "U4") (pin "B36") (pinfunction "GPIO29(USB_HS_D_-)_B36") (pintype "bidirectional"))
      (node (ref "U4") (pin "B38") (pinfunction "+3V3_D_B38") (pintype "bidirectional"))
    )
    (net (code "171") (name "SCLK_2") (class "Default")
      (node (ref "U3") (pin "9") (pinfunction "GPIO8(SPI1_SCK)_9") (pintype "bidirectional"))
      (node (ref "U3") (pin "B9") (pinfunction "GPIO8(SPI1_SCK)_B9") (pintype "bidirectional"))
      (node (ref "U4") (pin "9") (pinfunction "GPIO8(SPI1_SCK)_9") (pintype "bidirectional"))
      (node (ref "U4") (pin "B9") (pinfunction "GPIO8(SPI1_SCK)_B9") (pintype "bidirectional"))
      (node (ref "U5") (pin "9") (pinfunction "GPIO8(SPI1_SCK)_9") (pintype "bidirectional"))
      (node (ref "U5") (pin "B9") (pinfunction "GPIO8(SPI1_SCK)_B9") (pintype "bidirectional"))
      (node (ref "U6") (pin "9") (pinfunction "GPIO8(SPI1_SCK)_9") (pintype "bidirectional"))
      (node (ref "U6") (pin "B9") (pinfunction "GPIO8(SPI1_SCK)_B9") (pintype "bidirectional"))
      (node (ref "U7") (pin "9") (pinfunction "GPIO8(SPI1_SCK)_9") (pintype "bidirectional"))
      (node (ref "U7") (pin "B9") (pinfunction "GPIO8(SPI1_SCK)_B9") (pintype "bidirectional"))
      (node (ref "U8") (pin "9") (pinfunction "GPIO8(SPI1_SCK)_9") (pintype "bidirectional"))
      (node (ref "U8") (pin "B9") (pinfunction "GPIO8(SPI1_SCK)_B9") (pintype "bidirectional"))
      (node (ref "X1") (pin "10") (pinfunction "KL_10") (pintype "passive"))
    )
    (net (code "172") (name "SD_CLK") (class "Default")
      (node (ref "R32") (pin "1") (pinfunction "1_1") (pintype "passive"))
      (node (ref "U7") (pin "7") (pinfunction "GPIO6(SDMMC1_CK)_7") (pintype "bidirectional"))
      (node (ref "U7") (pin "B7") (pinfunction "GPIO6(SDMMC1_CK)_B7") (pintype "bidirectional"))
    )
    (net (code "173") (name "SD_CMD") (class "Default")
      (node (ref "R31") (pin "1") (pinfunction "1_1") (pintype "passive"))
      (node (ref "R95") (pin "1") (pinfunction "1_1") (pintype "passive"))
      (node (ref "U7") (pin "6") (pinfunction "GPIO5(SDMMC1_CMD)_6") (pintype "bidirectional"))
      (node (ref "U7") (pin "B6") (pinfunction "GPIO5(SDMMC1_CMD)_B6") (pintype "bidirectional"))
    )
    (net (code "174") (name "SD_DAT0") (class "Default")
      (node (ref "R33") (pin "1") (pinfunction "1_1") (pintype "passive"))
      (node (ref "R94") (pin "1") (pinfunction "1_1") (pintype "passive"))
      (node (ref "U7") (pin "5") (pinfunction "GPIO4(SDMMC1_D0)_5") (pintype "bidirectional"))
      (node (ref "U7") (pin "B5") (pinfunction "GPIO4(SDMMC1_D0)_B5") (pintype "bidirectional"))
    )
    (net (code "175") (name "SD_DAT1") (class "Default")
      (node (ref "R34") (pin "1") (pinfunction "1_1") (pintype "passive"))
      (node (ref "R93") (pin "1") (pinfunction "1_1") (pintype "passive"))
      (node (ref "U7") (pin "4") (pinfunction "GPIO3(SDMMC1_D1)_4") (pintype "bidirectional"))
      (node (ref "U7") (pin "B4") (pinfunction "GPIO3(SDMMC1_D1)_B4") (pintype "bidirectional"))
    )
    (net (code "176") (name "SD_DAT2") (class "Default")
      (node (ref "R29") (pin "1") (pinfunction "1_1") (pintype "passive"))
      (node (ref "R97") (pin "1") (pinfunction "1_1") (pintype "passive"))
      (node (ref "U7") (pin "3") (pinfunction "GPIO2(SDMMC1_D2)_3") (pintype "bidirectional"))
      (node (ref "U7") (pin "B3") (pinfunction "GPIO2(SDMMC1_D2)_B3") (pintype "bidirectional"))
    )
    (net (code "177") (name "SD_DAT3") (class "Default")
      (node (ref "R30") (pin "1") (pinfunction "1_1") (pintype "passive"))
      (node (ref "R96") (pin "1") (pinfunction "1_1") (pintype "passive"))
      (node (ref "U7") (pin "2") (pinfunction "GPIO1(SDMMC1_D3)_2") (pintype "bidirectional"))
      (node (ref "U7") (pin "B2") (pinfunction "GPIO1(SDMMC1_D3)_B2") (pintype "bidirectional"))
    )
    (net (code "178") (name "SPI6_CLK") (class "Default")
      (node (ref "U3") (pin "29") (pinfunction "GPIO22(ADC7/DAC2)_29") (pintype "bidirectional"))
      (node (ref "U3") (pin "B29") (pinfunction "GPIO22(ADC7/DAC2)_B29") (pintype "bidirectional"))
      (node (ref "U4") (pin "29") (pinfunction "GPIO22(ADC7/DAC2)_29") (pintype "bidirectional"))
      (node (ref "U4") (pin "B29") (pinfunction "GPIO22(ADC7/DAC2)_B29") (pintype "bidirectional"))
      (node (ref "U5") (pin "29") (pinfunction "GPIO22(ADC7/DAC2)_29") (pintype "bidirectional"))
      (node (ref "U5") (pin "B29") (pinfunction "GPIO22(ADC7/DAC2)_B29") (pintype "bidirectional"))
      (node (ref "U6") (pin "29") (pinfunction "GPIO22(ADC7/DAC2)_29") (pintype "bidirectional"))
      (node (ref "U6") (pin "B29") (pinfunction "GPIO22(ADC7/DAC2)_B29") (pintype "bidirectional"))
      (node (ref "U7") (pin "29") (pinfunction "GPIO22(ADC7/DAC2)_29") (pintype "bidirectional"))
      (node (ref "U7") (pin "B29") (pinfunction "GPIO22(ADC7/DAC2)_B29") (pintype "bidirectional"))
      (node (ref "U8") (pin "29") (pinfunction "GPIO22(ADC7/DAC2)_29") (pintype "bidirectional"))
      (node (ref "U8") (pin "B29") (pinfunction "GPIO22(ADC7/DAC2)_B29") (pintype "bidirectional"))
      (node (ref "X1") (pin "6") (pinfunction "KL_6") (pintype "passive"))
    )
    (net (code "179") (name "SPI6_MOSI") (class "Default")
      (node (ref "U3") (pin "25") (pinfunction "GPIO18(ADC3)_25") (pintype "bidirectional"))
      (node (ref "U3") (pin "B25") (pinfunction "GPIO18(ADC3)_B25") (pintype "bidirectional"))
      (node (ref "U4") (pin "25") (pinfunction "GPIO18(ADC3)_25") (pintype "bidirectional"))
      (node (ref "U4") (pin "B25") (pinfunction "GPIO18(ADC3)_B25") (pintype "bidirectional"))
      (node (ref "U5") (pin "25") (pinfunction "GPIO18(ADC3)_25") (pintype "bidirectional"))
      (node (ref "U5") (pin "B25") (pinfunction "GPIO18(ADC3)_B25") (pintype "bidirectional"))
      (node (ref "U6") (pin "25") (pinfunction "GPIO18(ADC3)_25") (pintype "bidirectional"))
      (node (ref "U6") (pin "B25") (pinfunction "GPIO18(ADC3)_B25") (pintype "bidirectional"))
      (node (ref "U7") (pin "25") (pinfunction "GPIO18(ADC3)_25") (pintype "bidirectional"))
      (node (ref "U7") (pin "B25") (pinfunction "GPIO18(ADC3)_B25") (pintype "bidirectional"))
      (node (ref "U8") (pin "25") (pinfunction "GPIO18(ADC3)_25") (pintype "bidirectional"))
      (node (ref "U8") (pin "B25") (pinfunction "GPIO18(ADC3)_B25") (pintype "bidirectional"))
      (node (ref "X1") (pin "8") (pinfunction "KL_8") (pintype "passive"))
    )
    (net (code "180") (name "SPI6_NSS") (class "Default")
      (node (ref "U3") (pin "30") (pinfunction "GPIO23(ADC8/DAC1)_30") (pintype "bidirectional"))
      (node (ref "U3") (pin "B30") (pinfunction "GPIO23(ADC8/DAC1)_B30") (pintype "bidirectional"))
      (node (ref "U4") (pin "30") (pinfunction "GPIO23(ADC8/DAC1)_30") (pintype "bidirectional"))
      (node (ref "U4") (pin "B30") (pinfunction "GPIO23(ADC8/DAC1)_B30") (pintype "bidirectional"))
      (node (ref "U5") (pin "30") (pinfunction "GPIO23(ADC8/DAC1)_30") (pintype "bidirectional"))
      (node (ref "U5") (pin "B30") (pinfunction "GPIO23(ADC8/DAC1)_B30") (pintype "bidirectional"))
      (node (ref "U6") (pin "30") (pinfunction "GPIO23(ADC8/DAC1)_30") (pintype "bidirectional"))
      (node (ref "U6") (pin "B30") (pinfunction "GPIO23(ADC8/DAC1)_B30") (pintype "bidirectional"))
      (node (ref "U7") (pin "30") (pinfunction "GPIO23(ADC8/DAC1)_30") (pintype "bidirectional"))
      (node (ref "U7") (pin "B30") (pinfunction "GPIO23(ADC8/DAC1)_B30") (pintype "bidirectional"))
      (node (ref "U8") (pin "30") (pinfunction "GPIO23(ADC8/DAC1)_30") (pintype "bidirectional"))
      (node (ref "U8") (pin "B30") (pinfunction "GPIO23(ADC8/DAC1)_B30") (pintype "bidirectional"))
      (node (ref "X1") (pin "5") (pinfunction "KL_5") (pintype "passive"))
    )
    (net (code "181") (name "SS_2") (class "Default")
      (node (ref "U3") (pin "8") (pinfunction "GPIO7(SPI1_NSS)_8") (pintype "bidirectional"))
      (node (ref "U3") (pin "B8") (pinfunction "GPIO7(SPI1_NSS)_B8") (pintype "bidirectional"))
      (node (ref "U4") (pin "8") (pinfunction "GPIO7(SPI1_NSS)_8") (pintype "bidirectional"))
      (node (ref "U4") (pin "B8") (pinfunction "GPIO7(SPI1_NSS)_B8") (pintype "bidirectional"))
      (node (ref "U5") (pin "8") (pinfunction "GPIO7(SPI1_NSS)_8") (pintype "bidirectional"))
      (node (ref "U5") (pin "B8") (pinfunction "GPIO7(SPI1_NSS)_B8") (pintype "bidirectional"))
      (node (ref "U6") (pin "8") (pinfunction "GPIO7(SPI1_NSS)_8") (pintype "bidirectional"))
      (node (ref "U6") (pin "B8") (pinfunction "GPIO7(SPI1_NSS)_B8") (pintype "bidirectional"))
      (node (ref "U7") (pin "8") (pinfunction "GPIO7(SPI1_NSS)_8") (pintype "bidirectional"))
      (node (ref "U7") (pin "B8") (pinfunction "GPIO7(SPI1_NSS)_B8") (pintype "bidirectional"))
      (node (ref "U8") (pin "8") (pinfunction "GPIO7(SPI1_NSS)_8") (pintype "bidirectional"))
      (node (ref "U8") (pin "B8") (pinfunction "GPIO7(SPI1_NSS)_B8") (pintype "bidirectional"))
      (node (ref "X1") (pin "9") (pinfunction "KL_9") (pintype "passive"))
    )
    (net (code "182") (name "unconnected-(PS1-NC-Pad3)") (class "Default")
      (node (ref "PS1") (pin "3") (pinfunction "NC_3") (pintype "no_connect"))
    )
    (net (code "183") (name "unconnected-(PS1-NC-Pad5)") (class "Default")
      (node (ref "PS1") (pin "5") (pinfunction "NC_5") (pintype "no_connect"))
    )
    (net (code "184") (name "unconnected-(X1E-KL-Pad13)") (class "Default")
      (node (ref "X1") (pin "13") (pinfunction "KL_13") (pintype "passive"))
    )
    (net (code "185") (name "unconnected-(X1F-KL-Pad14)") (class "Default")
      (node (ref "X1") (pin "14") (pinfunction "KL_14") (pintype "passive"))
    )
    (net (code "186") (name "unconnected-(X1G-KL-Pad15)") (class "Default")
      (node (ref "X1") (pin "15") (pinfunction "KL_15") (pintype "passive"))
    )
    (net (code "187") (name "unconnected-(X1H-KL-Pad16)") (class "Default")
      (node (ref "X1") (pin "16") (pinfunction "KL_16") (pintype "passive"))
    )
    (net (code "188") (name "unconnected-(X1N-KL-Pad7)") (class "Default")
      (node (ref "X1") (pin "7") (pinfunction "KL_7") (pintype "passive"))
    )
  )
)
